# tottag.net
KiCad netlist of a schematic drawn in EAGLE
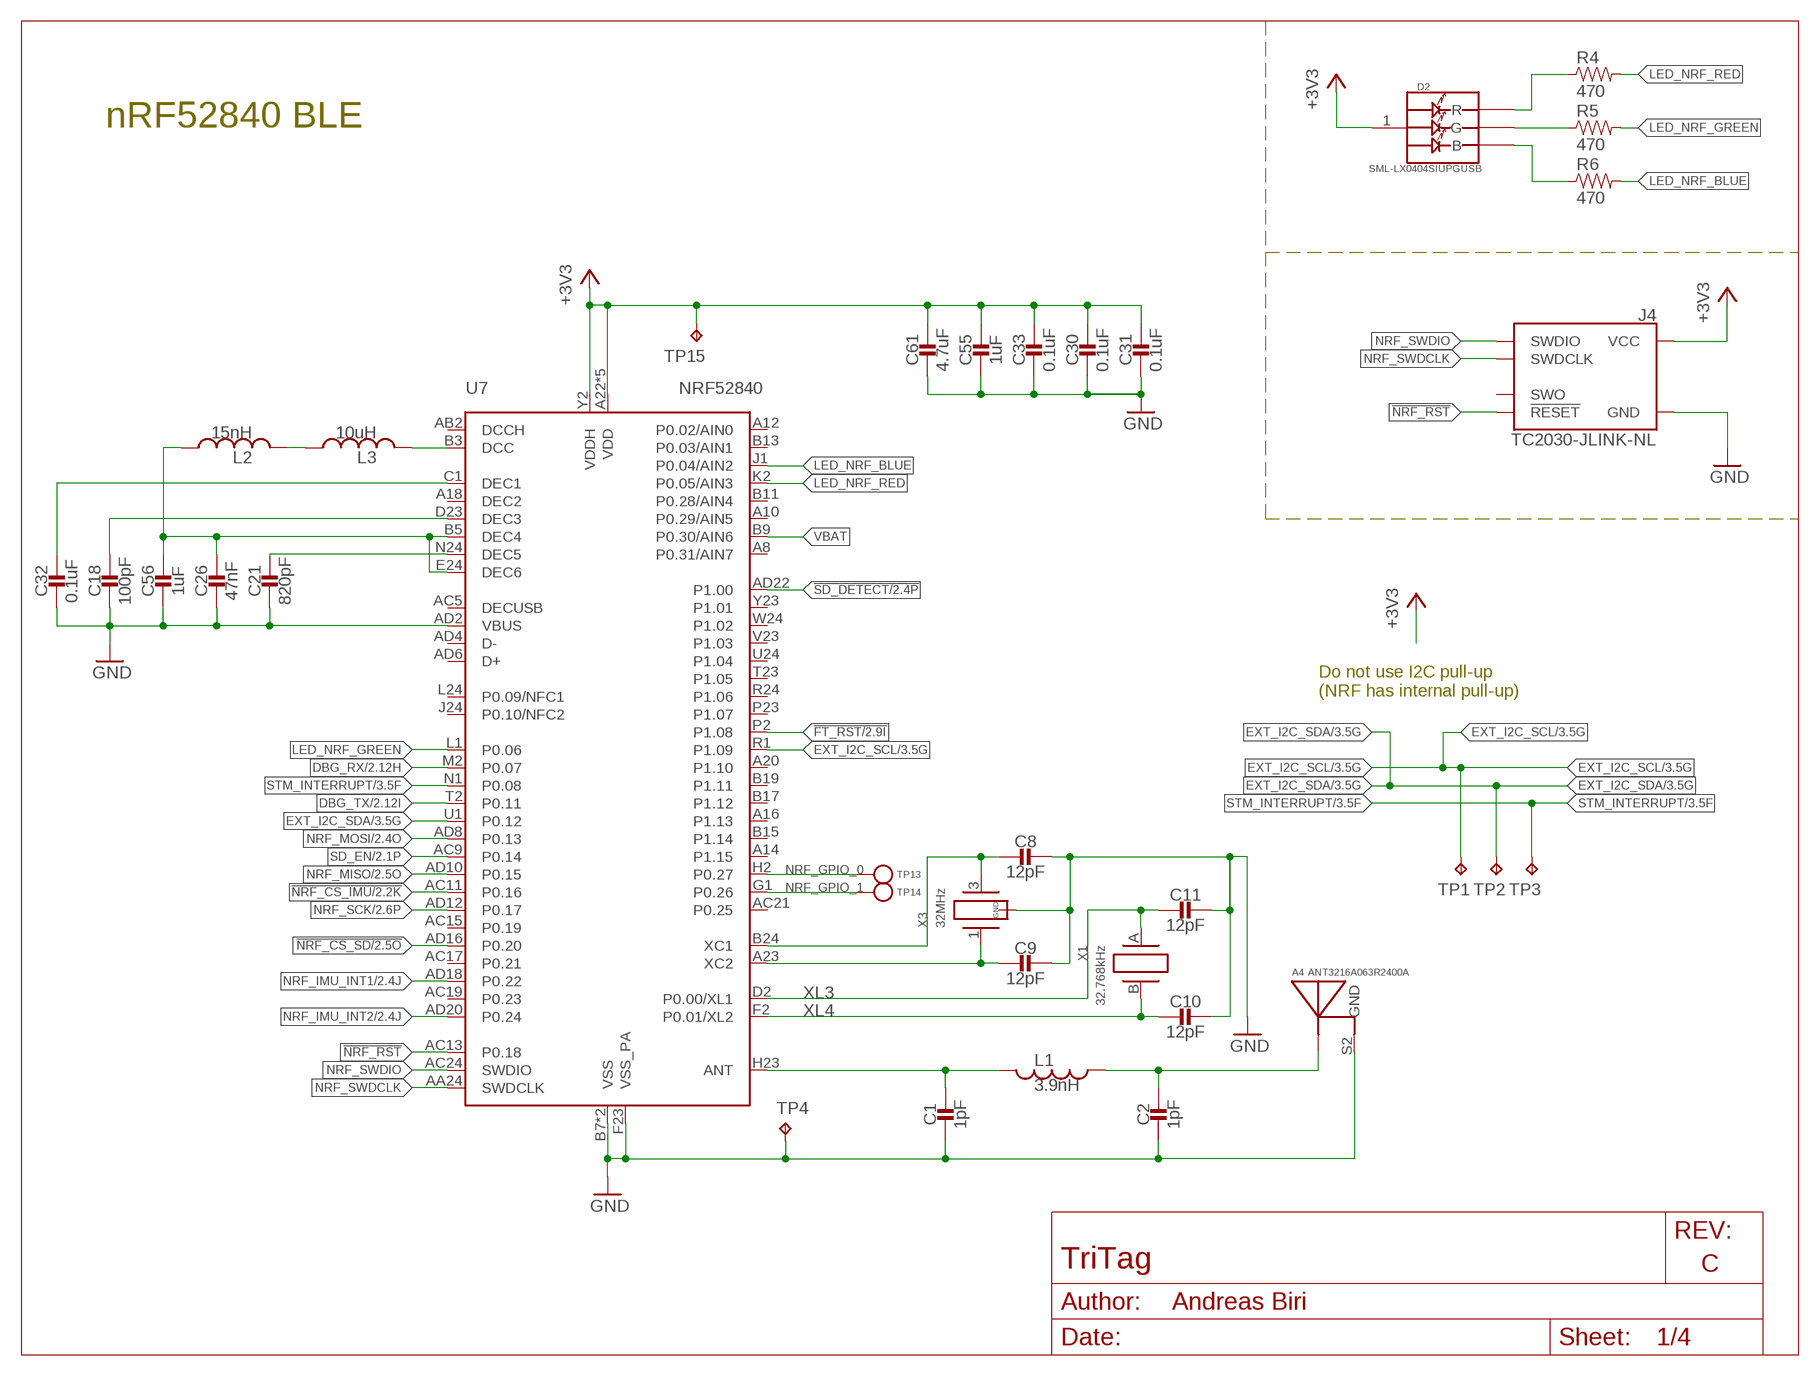
[diagram p0: schematic, sheet 1]
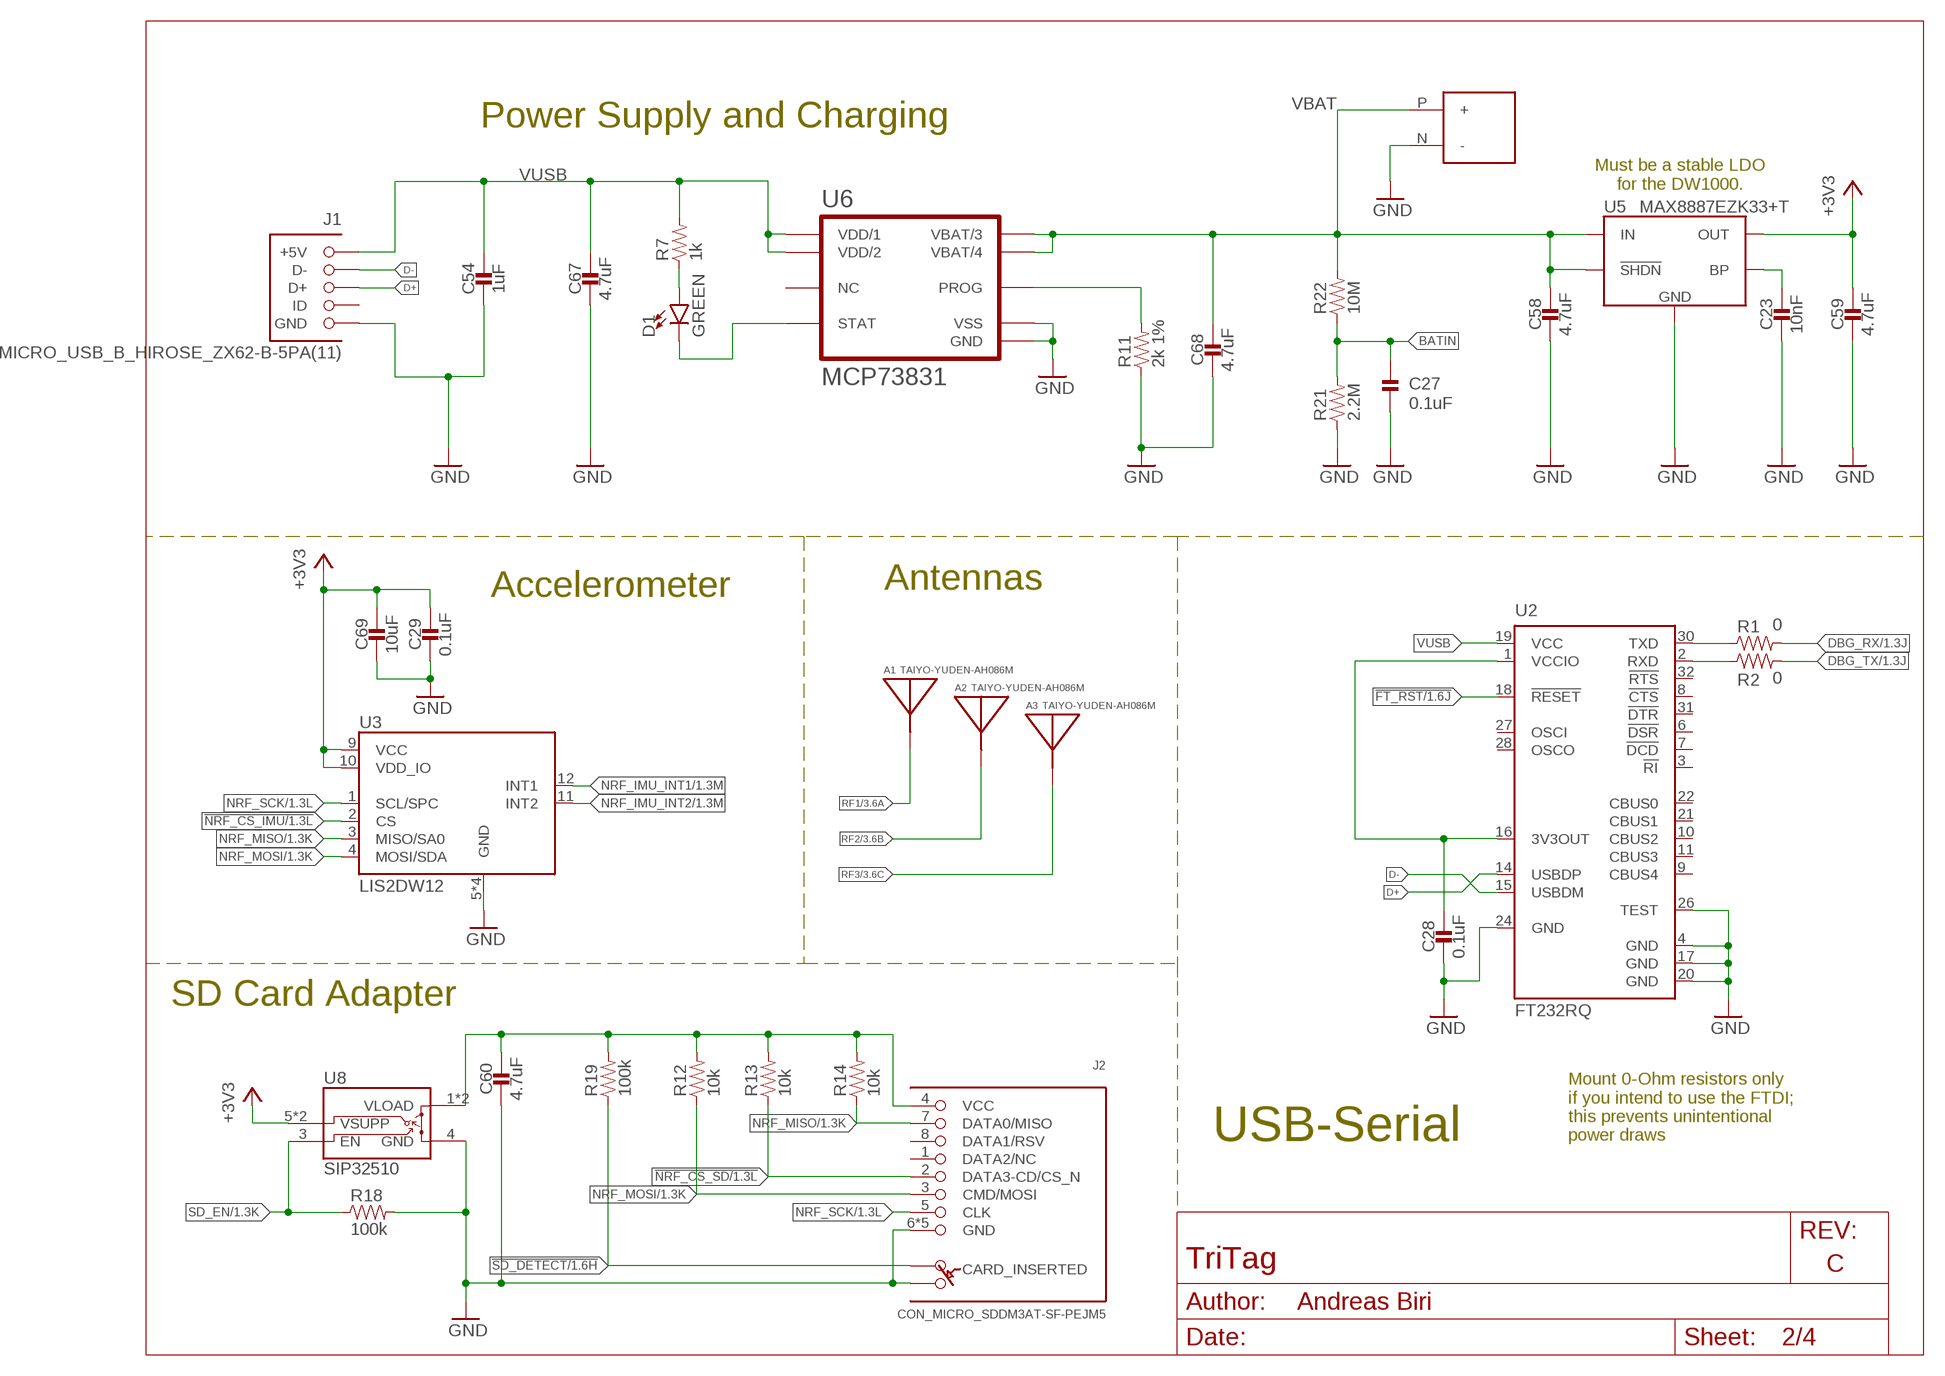
[diagram p1: schematic, sheet 2]
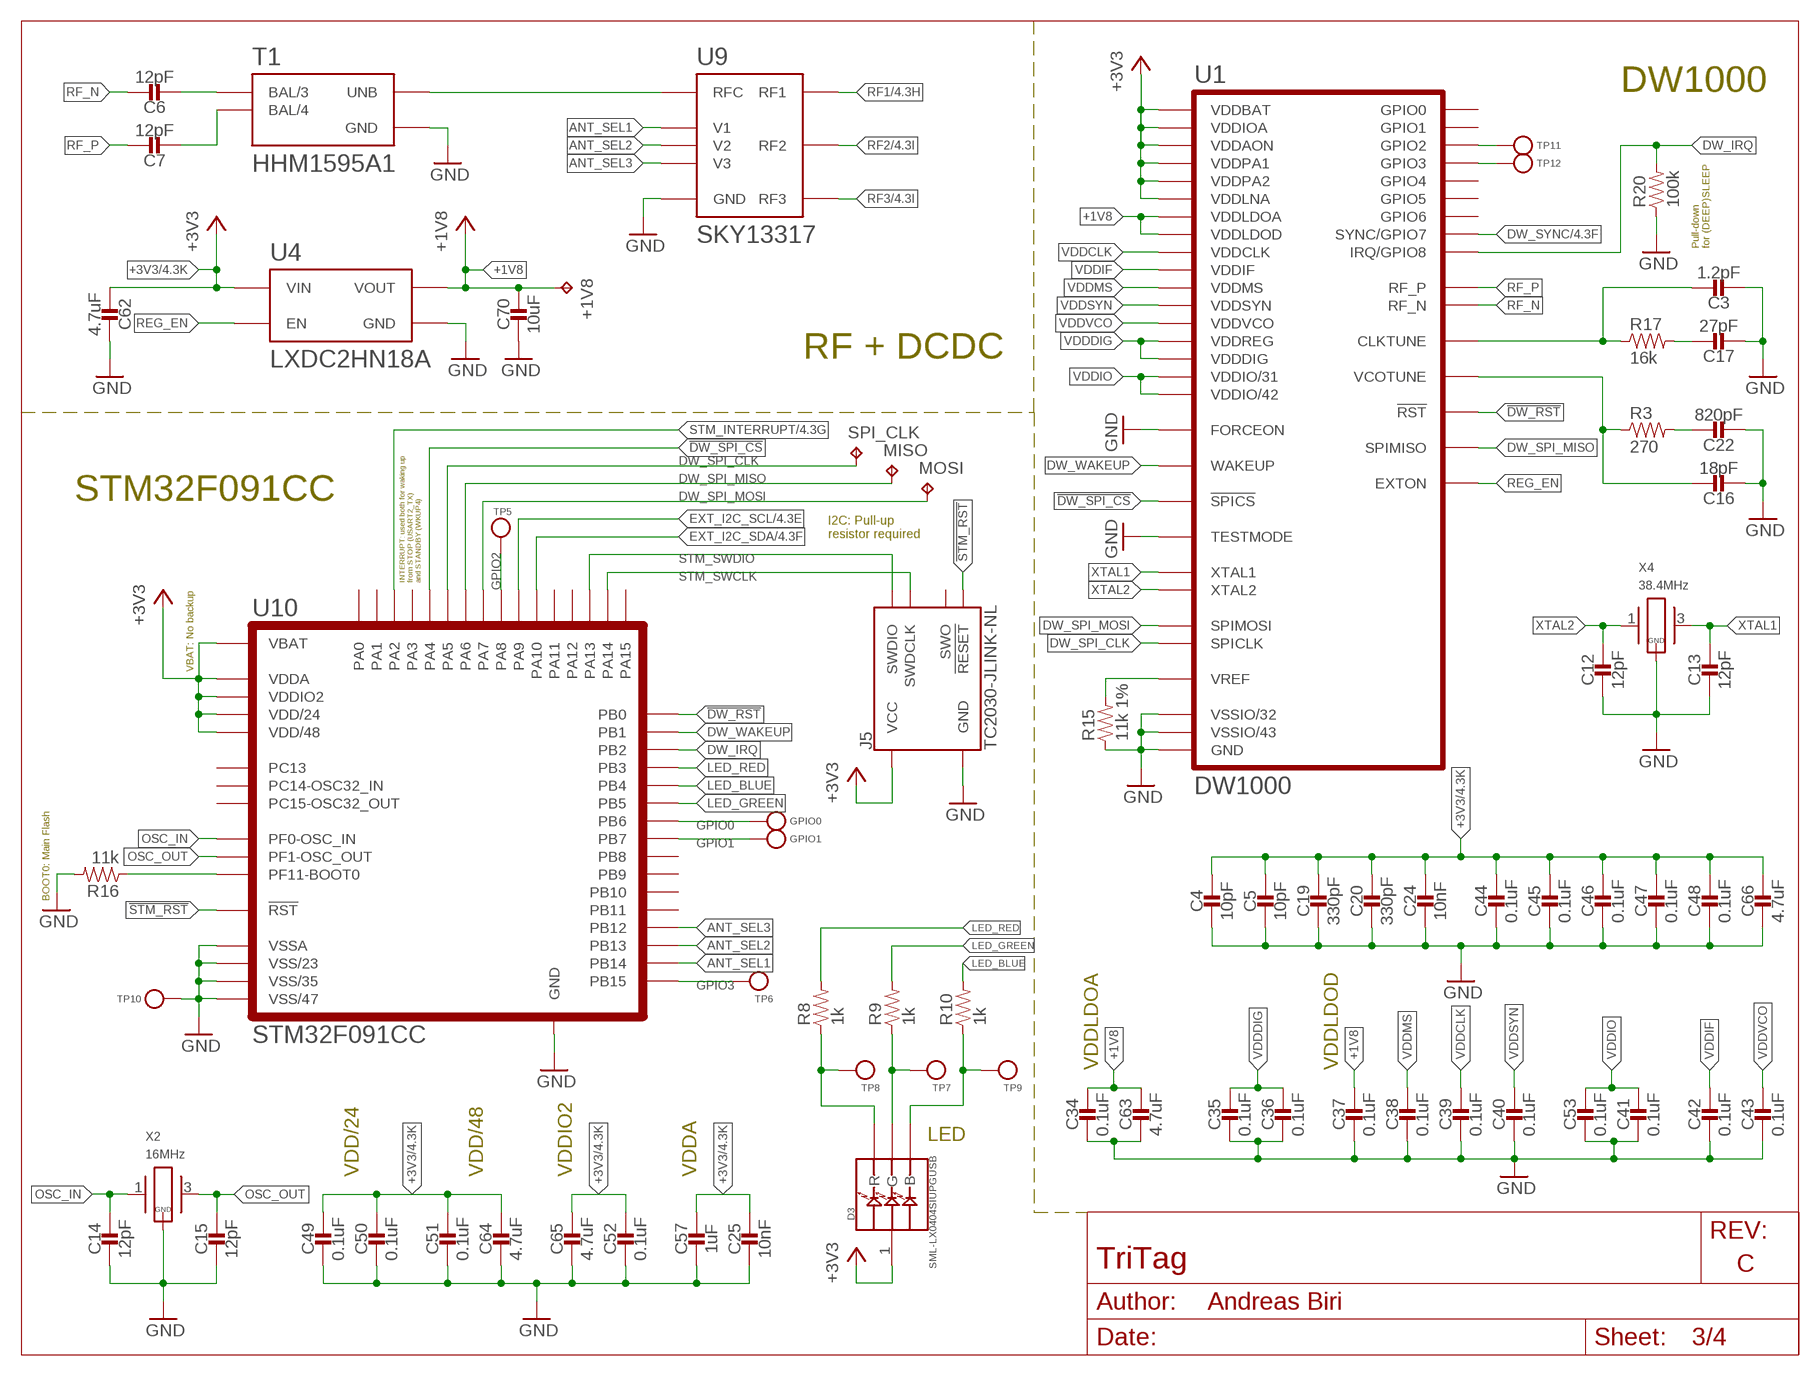
[diagram p2: schematic, sheet 3]
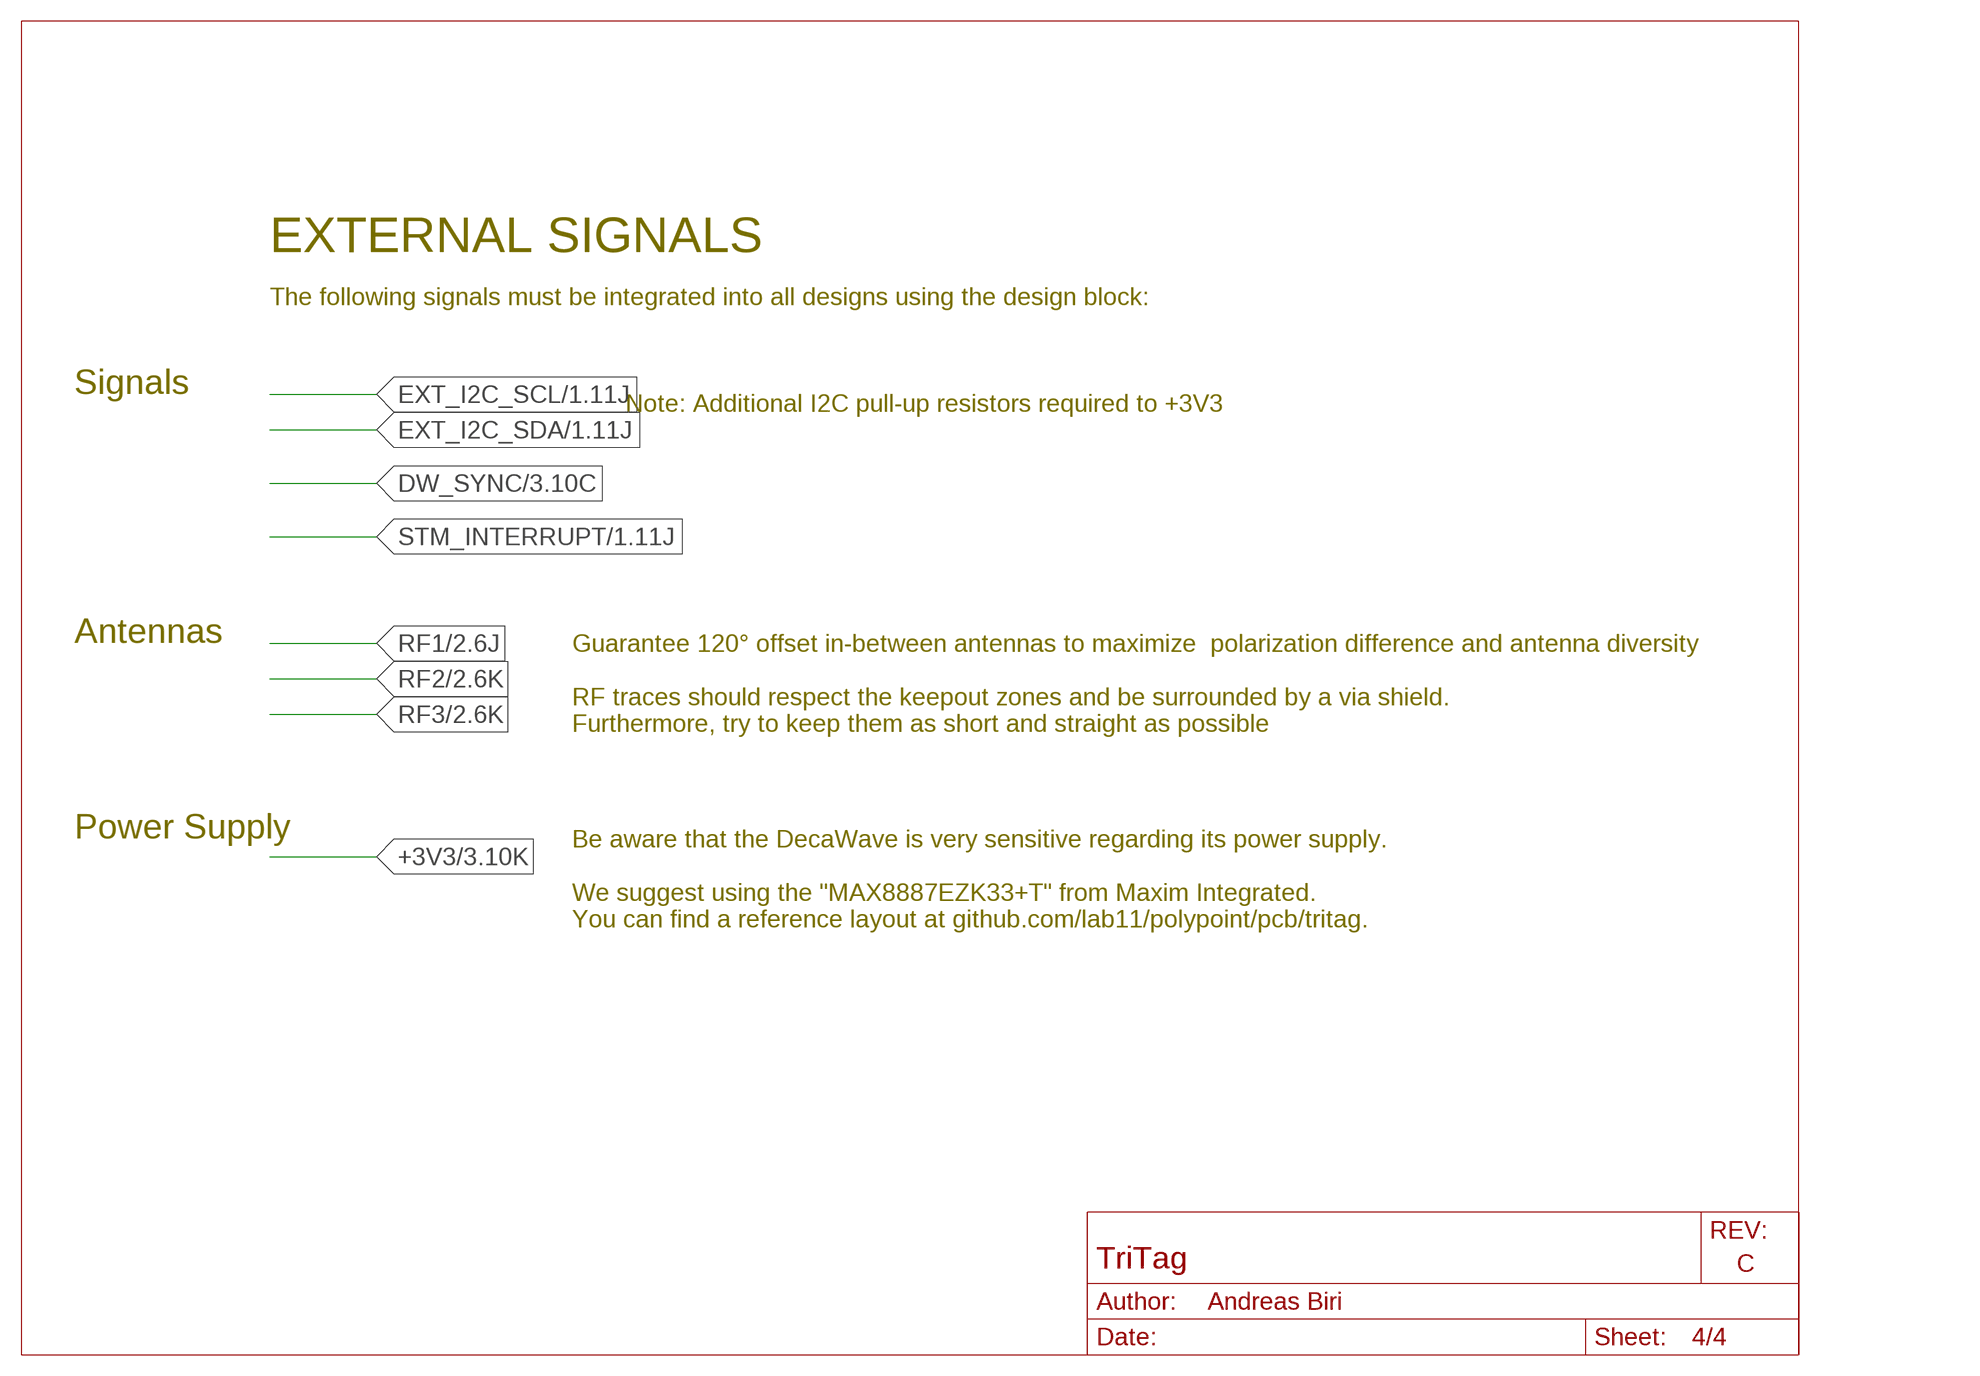
[diagram p3: schematic, sheet 4]

(export (version "E")
  (design (tool "Eeschema 10.0.6"))
  (components
    (comp (ref "A1")
      (value "TAIYO-YUDEN-AH086M")
      (footprint "eagle-import:TAIYO-YUDEN-AH086M")
      (libsource (lib "eagle-import") (part "TAIYO-YUDEN-AH086M"))
    )
    (comp (ref "A2")
      (value "TAIYO-YUDEN-AH086M")
      (footprint "eagle-import:TAIYO-YUDEN-AH086M")
      (libsource (lib "eagle-import") (part "TAIYO-YUDEN-AH086M"))
    )
    (comp (ref "A3")
      (value "TAIYO-YUDEN-AH086M")
      (footprint "eagle-import:TAIYO-YUDEN-AH086M")
      (libsource (lib "eagle-import") (part "TAIYO-YUDEN-AH086M"))
    )
    (comp (ref "C23")
      (value "10nF")
      (footprint "eagle-import:0402_CAP")
      (libsource (lib "eagle-import") (part "CAPACITOR0402_CAP"))
    )
    (comp (ref "C27")
      (value "0.1uF")
      (footprint "eagle-import:0402_CAP")
      (libsource (lib "eagle-import") (part "CAPACITOR0402_CAP"))
    )
    (comp (ref "C28")
      (value "0.1uF")
      (footprint "eagle-import:0402_CAP")
      (fields (field (name "MPN") "GRM155R71C104KA88J "))
      (libsource (lib "eagle-import") (part "CAPACITOR0402_CAP"))
    )
    (comp (ref "C29")
      (value "0.1uF")
      (footprint "eagle-import:0402_CAP")
      (fields (field (name "MPN") "GRM155R71C104KA88J "))
      (libsource (lib "eagle-import") (part "CAPACITOR0402_CAP"))
    )
    (comp (ref "C54")
      (value "1uF")
      (footprint "eagle-import:0402_CAP")
      (libsource (lib "eagle-import") (part "CAPACITOR0402_CAP"))
    )
    (comp (ref "C58")
      (value "4.7uF")
      (footprint "eagle-import:0402_CAP")
      (libsource (lib "eagle-import") (part "CAPACITOR0402_CAP"))
    )
    (comp (ref "C59")
      (value "4.7uF")
      (footprint "eagle-import:0402_CAP")
      (libsource (lib "eagle-import") (part "CAPACITOR0402_CAP"))
    )
    (comp (ref "C60")
      (value "4.7uF")
      (footprint "eagle-import:0402_CAP")
      (description "CAP CER 4.7UF 6.3V X5R 0402")
      (fields (field (name "MANUFACTURER") "TDK") (field (name "MPN") "C1005X5R0J475K050BC"))
      (libsource (lib "eagle-import") (part "CAPACITOR0402_CAP"))
    )
    (comp (ref "C67")
      (value "4.7uF")
      (footprint "eagle-import:0402_CAP")
      (libsource (lib "eagle-import") (part "CAPACITOR0402_CAP"))
    )
    (comp (ref "C68")
      (value "4.7uF")
      (footprint "eagle-import:0402_CAP")
      (libsource (lib "eagle-import") (part "CAPACITOR0402_CAP"))
    )
    (comp (ref "C69")
      (value "10uF")
      (footprint "eagle-import:0603_CAP")
      (fields (field (name "MPN") "GRM188R60J106ME47D "))
      (libsource (lib "eagle-import") (part "CAPACITOR0603_CAP"))
    )
    (comp (ref "D1")
      (value "GREEN")
      (footprint "eagle-import:LED-0603")
      (libsource (lib "eagle-import") (part "LED0603"))
    )
    (comp (ref "J1")
      (value "MICRO_USB_B_HIROSE_ZX62-B-5PA(11)")
      (footprint "eagle-import:USB_MICRO_B-HIROSE-ZX62-B-5PA(11)")
      (libsource (lib "eagle-import") (part "MICRO_USB_B_HIROSE_ZX62-B-5PA(11)"))
    )
    (comp (ref "J2")
      (value "CON_MICRO_SDDM3AT-SF-PEJM5")
      (footprint "eagle-import:DM3AT-SF-PEJM5")
      (libsource (lib "eagle-import") (part "CON_MICRO_SDDM3AT-SF-PEJM5"))
    )
    (comp (ref "J3")
      (value "BAT_HOLE")
      (footprint "eagle-import:BATTERY_HOLE")
      (libsource (lib "eagle-import") (part "BAT_HOLE"))
    )
    (comp (ref "R1")
      (value "0")
      (footprint "eagle-import:0402_RES")
      (libsource (lib "eagle-import") (part "RESISTOR0402_RES"))
    )
    (comp (ref "R2")
      (value "0")
      (footprint "eagle-import:0402_RES")
      (libsource (lib "eagle-import") (part "RESISTOR0402_RES"))
    )
    (comp (ref "R7")
      (value "1k")
      (footprint "eagle-import:0402_RES")
      (libsource (lib "eagle-import") (part "RESISTOR0402_RES"))
    )
    (comp (ref "R11")
      (value "2k 1%")
      (footprint "eagle-import:0402_RES")
      (libsource (lib "eagle-import") (part "RESISTOR0402_RES"))
    )
    (comp (ref "R12")
      (value "10k")
      (footprint "eagle-import:0402_RES")
      (libsource (lib "eagle-import") (part "RESISTOR0402_RES"))
    )
    (comp (ref "R13")
      (value "10k")
      (footprint "eagle-import:0402_RES")
      (libsource (lib "eagle-import") (part "RESISTOR0402_RES"))
    )
    (comp (ref "R14")
      (value "10k")
      (footprint "eagle-import:0402_RES")
      (libsource (lib "eagle-import") (part "RESISTOR0402_RES"))
    )
    (comp (ref "R18")
      (value "100k")
      (footprint "eagle-import:0402_RES")
      (libsource (lib "eagle-import") (part "RESISTOR0402_RES"))
    )
    (comp (ref "R19")
      (value "100k")
      (footprint "eagle-import:0402_RES")
      (libsource (lib "eagle-import") (part "RESISTOR0402_RES"))
    )
    (comp (ref "R21")
      (value "2.2M")
      (footprint "eagle-import:0402_RES")
      (libsource (lib "eagle-import") (part "RESISTOR0402_RES"))
    )
    (comp (ref "R22")
      (value "10M")
      (footprint "eagle-import:0402_RES")
      (libsource (lib "eagle-import") (part "RESISTOR0402_RES"))
    )
    (comp (ref "U2")
      (value "FT232RQ")
      (footprint "eagle-import:QFN32")
      (libsource (lib "eagle-import") (part "FT232RQ"))
    )
    (comp (ref "U3")
      (value "LIS2DW12")
      (footprint "eagle-import:LGA-12")
      (fields (field (name "MANUFACTURER") "STMicroelectronics") (field (name "MPN") "LIS2DW12TR"))
      (libsource (lib "eagle-import") (part "LIS2DW12"))
    )
    (comp (ref "U5")
      (value "MAX8887EZK33+T")
      (footprint "eagle-import:SOT-23-5")
      (libsource (lib "eagle-import") (part "MAX8887EZK33+T"))
    )
    (comp (ref "U6")
      (value "MCP73831")
      (footprint "eagle-import:DFN-8-MCP")
      (fields (field (name "MANUFACTURER") "Microchip Technology") (field (name "MPN") "MCP73831T-2ACI/MC"))
      (libsource (lib "eagle-import") (part "MCP73831"))
    )
    (comp (ref "U8")
      (value "SIP32510")
      (footprint "eagle-import:TSOT23-6")
      (fields (field (name "MANUFACTURER") "Vishay") (field (name "MPN") "SIP32510DT-T1-GE3"))
      (libsource (lib "eagle-import") (part "SIP32510"))
    )
    (comp (ref "A4")
      (value "ANT3216A063R2400A")
      (footprint "eagle-import:ANT3216A063R2400A")
      (fields (field (name "MANUFACTURER") "YAGEO"))
      (libsource (lib "eagle-import") (part "ANT3216A063R2400A"))
    )
    (comp (ref "C1")
      (value "1pF")
      (footprint "eagle-import:0402_CAP")
      (fields (field (name "MPN") "GJM1555C1H1R0CB01D "))
      (libsource (lib "eagle-import") (part "CAPACITOR0402_CAP"))
    )
    (comp (ref "C2")
      (value "1pF")
      (footprint "eagle-import:0402_CAP")
      (fields (field (name "MPN") "GJM1555C1H1R0CB01D"))
      (libsource (lib "eagle-import") (part "CAPACITOR0402_CAP"))
    )
    (comp (ref "C8")
      (value "12pF")
      (footprint "eagle-import:0402_CAP")
      (fields (field (name "MPN") "GRM1555C1H120GA01D "))
      (libsource (lib "eagle-import") (part "CAPACITOR0402_CAP"))
    )
    (comp (ref "C9")
      (value "12pF")
      (footprint "eagle-import:0402_CAP")
      (fields (field (name "MPN") "GRM1555C1H120GA01D "))
      (libsource (lib "eagle-import") (part "CAPACITOR0402_CAP"))
    )
    (comp (ref "C10")
      (value "12pF")
      (footprint "eagle-import:0402_CAP")
      (fields (field (name "MPN") "GRM1555C1H120GA01D "))
      (libsource (lib "eagle-import") (part "CAPACITOR0402_CAP"))
    )
    (comp (ref "C11")
      (value "12pF")
      (footprint "eagle-import:0402_CAP")
      (fields (field (name "MPN") "GRM1555C1H120GA01D "))
      (libsource (lib "eagle-import") (part "CAPACITOR0402_CAP"))
    )
    (comp (ref "C18")
      (value "100pF")
      (footprint "eagle-import:0402_CAP")
      (fields (field (name "MPN") "GRM1555C1H101JA01D "))
      (libsource (lib "eagle-import") (part "CAPACITOR0402_CAP"))
    )
    (comp (ref "C21")
      (value "820pF")
      (footprint "eagle-import:0402_CAP")
      (fields (field (name "MPN") "CL05C821JB5NFNC"))
      (libsource (lib "eagle-import") (part "CAPACITOR0402_CAP"))
    )
    (comp (ref "C26")
      (value "47nF")
      (footprint "eagle-import:0402_CAP")
      (fields (field (name "MPN") "C1005X7R1C473K050BC "))
      (libsource (lib "eagle-import") (part "CAPACITOR0402_CAP"))
    )
    (comp (ref "C30")
      (value "0.1uF")
      (footprint "eagle-import:0402_CAP")
      (fields (field (name "MPN") "GRM155R71C104KA88J "))
      (libsource (lib "eagle-import") (part "CAPACITOR0402_CAP"))
    )
    (comp (ref "C31")
      (value "0.1uF")
      (footprint "eagle-import:0402_CAP")
      (fields (field (name "MPN") "GRM155R71C104KA88J "))
      (libsource (lib "eagle-import") (part "CAPACITOR0402_CAP"))
    )
    (comp (ref "C32")
      (value "0.1uF")
      (footprint "eagle-import:0402_CAP")
      (fields (field (name "MPN") "GRM155R71C104KA88J "))
      (libsource (lib "eagle-import") (part "CAPACITOR0402_CAP"))
    )
    (comp (ref "C33")
      (value "0.1uF")
      (footprint "eagle-import:0402_CAP")
      (fields (field (name "MPN") "GRM155R71C104KA88J "))
      (libsource (lib "eagle-import") (part "CAPACITOR0402_CAP"))
    )
    (comp (ref "C55")
      (value "1uF")
      (footprint "eagle-import:0402_CAP")
      (fields (field (name "MPN") "GRM155R70G105KA12D "))
      (libsource (lib "eagle-import") (part "CAPACITOR0402_CAP"))
    )
    (comp (ref "C56")
      (value "1uF")
      (footprint "eagle-import:0402_CAP")
      (fields (field (name "MPN") "GRM155R70G105KA12D "))
      (libsource (lib "eagle-import") (part "CAPACITOR0402_CAP"))
    )
    (comp (ref "C61")
      (value "4.7uF")
      (footprint "eagle-import:0402_CAP")
      (fields (field (name "MPN") "C1005X5R0J475K050BC "))
      (libsource (lib "eagle-import") (part "CAPACITOR0402_CAP"))
    )
    (comp (ref "D2")
      (value "SML-LX0404SIUPGUSB")
      (footprint "eagle-import:1MM_SQ_4PAD")
      (fields (field (name "MANUFACTURER") "Lumex Opto"))
      (libsource (lib "eagle-import") (part "SML-LX0404SIUPGUSB"))
    )
    (comp (ref "J4")
      (value "TC2030-JLINK-NL")
      (footprint "eagle-import:TC2030-IDC-NL")
      (libsource (lib "eagle-import") (part "TC2030-JLINK-NL"))
    )
    (comp (ref "L1")
      (value "3.9nH")
      (footprint "eagle-import:0402_CAP")
      (fields (field (name "MPN") "AISC-0402-3N9G-T "))
      (libsource (lib "eagle-import") (part "INDUCTOR0402"))
    )
    (comp (ref "L2")
      (value "15nH")
      (footprint "eagle-import:0402_CAP")
      (fields (field (name "MPN") "HK100515NJ-T "))
      (libsource (lib "eagle-import") (part "INDUCTOR0402"))
    )
    (comp (ref "L3")
      (value "10uH")
      (footprint "eagle-import:0603_CAP")
      (fields (field (name "MPN") "LQM18FN100M00D "))
      (libsource (lib "eagle-import") (part "INDUCTOR0603"))
    )
    (comp (ref "R4")
      (value "470")
      (footprint "eagle-import:0402_RES")
      (libsource (lib "eagle-import") (part "RESISTOR0402_RES"))
    )
    (comp (ref "R5")
      (value "470")
      (footprint "eagle-import:0402_RES")
      (libsource (lib "eagle-import") (part "RESISTOR0402_RES"))
    )
    (comp (ref "R6")
      (value "470")
      (footprint "eagle-import:0402_RES")
      (libsource (lib "eagle-import") (part "RESISTOR0402_RES"))
    )
    (comp (ref "TP1")
      (value "TPTP06SQ")
      (footprint "eagle-import:TP06SQ")
      (libsource (lib "eagle-import") (part "TPTP06SQ"))
    )
    (comp (ref "TP2")
      (value "TPTP06SQ")
      (footprint "eagle-import:TP06SQ")
      (libsource (lib "eagle-import") (part "TPTP06SQ"))
    )
    (comp (ref "TP3")
      (value "TPTP06SQ")
      (footprint "eagle-import:TP06SQ")
      (libsource (lib "eagle-import") (part "TPTP06SQ"))
    )
    (comp (ref "TP4")
      (value "TPTP06SQ")
      (footprint "eagle-import:TP06SQ")
      (libsource (lib "eagle-import") (part "TPTP06SQ"))
    )
    (comp (ref "TP13")
      (value "TEST-POINT")
      (footprint "eagle-import:PAD.03X.03")
      (libsource (lib "eagle-import") (part "TEST-POINT"))
    )
    (comp (ref "TP14")
      (value "TEST-POINT")
      (footprint "eagle-import:PAD.03X.03")
      (libsource (lib "eagle-import") (part "TEST-POINT"))
    )
    (comp (ref "TP15")
      (value "TPTP06SQ")
      (footprint "eagle-import:TP06SQ")
      (libsource (lib "eagle-import") (part "TPTP06SQ"))
    )
    (comp (ref "U7")
      (value "NRF52840")
      (footprint "eagle-import:AQFN73")
      (fields (field (name "MANUFACTURER") "NORIDIC SEMICONDUCTOR"))
      (libsource (lib "eagle-import") (part "NRF52840"))
    )
    (comp (ref "X1")
      (value "32.768kHz")
      (footprint "eagle-import:ABS05")
      (fields (field (name "MANUFACTURER") "Abracon") (field (name "MPN") "ABS05-32.768KHZ-9-T"))
      (libsource (lib "eagle-import") (part "ABS05-32.768KHZ-9-T"))
    )
    (comp (ref "X3")
      (value "32MHz")
      (footprint "eagle-import:TXC-7V")
      (fields (field (name "MANUFACTURER") "TXC CORPORATION") (field (name "MPN") "7M-32.000MAHV-T"))
      (libsource (lib "eagle-import") (part "7V-32.000MAHV-T"))
    )
    (comp (ref "+1V8")
      (value "TPTP06SQ")
      (footprint "eagle-import:TP06SQ")
      (libsource (lib "eagle-import") (part "TPTP06SQ"))
    )
    (comp (ref "C3")
      (value "1.2pF")
      (footprint "eagle-import:0402_CAP")
      (libsource (lib "eagle-import") (part "CAPACITOR0402_CAP"))
    )
    (comp (ref "C4")
      (value "10pF")
      (footprint "eagle-import:0402_CAP")
      (libsource (lib "eagle-import") (part "CAPACITOR0402_CAP"))
    )
    (comp (ref "C5")
      (value "10pF")
      (footprint "eagle-import:0402_CAP")
      (libsource (lib "eagle-import") (part "CAPACITOR0402_CAP"))
    )
    (comp (ref "C6")
      (value "12pF")
      (footprint "eagle-import:0201_CAP")
      (libsource (lib "eagle-import") (part "CAPACITOR0201_CAP"))
    )
    (comp (ref "C7")
      (value "12pF")
      (footprint "eagle-import:0201_CAP")
      (libsource (lib "eagle-import") (part "CAPACITOR0201_CAP"))
    )
    (comp (ref "C12")
      (value "12pF")
      (footprint "eagle-import:0402_CAP")
      (libsource (lib "eagle-import") (part "CAPACITOR0402_CAP"))
    )
    (comp (ref "C13")
      (value "12pF")
      (footprint "eagle-import:0402_CAP")
      (libsource (lib "eagle-import") (part "CAPACITOR0402_CAP"))
    )
    (comp (ref "C14")
      (value "12pF")
      (footprint "eagle-import:0402_CAP")
      (libsource (lib "eagle-import") (part "CAPACITOR0402_CAP"))
    )
    (comp (ref "C15")
      (value "12pF")
      (footprint "eagle-import:0402_CAP")
      (libsource (lib "eagle-import") (part "CAPACITOR0402_CAP"))
    )
    (comp (ref "C16")
      (value "18pF")
      (footprint "eagle-import:0402_CAP")
      (libsource (lib "eagle-import") (part "CAPACITOR0402_CAP"))
    )
    (comp (ref "C17")
      (value "27pF")
      (footprint "eagle-import:0402_CAP")
      (libsource (lib "eagle-import") (part "CAPACITOR0402_CAP"))
    )
    (comp (ref "C19")
      (value "330pF")
      (footprint "eagle-import:0402_CAP")
      (libsource (lib "eagle-import") (part "CAPACITOR0402_CAP"))
    )
    (comp (ref "C20")
      (value "330pF")
      (footprint "eagle-import:0402_CAP")
      (libsource (lib "eagle-import") (part "CAPACITOR0402_CAP"))
    )
    (comp (ref "C22")
      (value "820pF")
      (footprint "eagle-import:0402_CAP")
      (libsource (lib "eagle-import") (part "CAPACITOR0402_CAP"))
    )
    (comp (ref "C24")
      (value "10nF")
      (footprint "eagle-import:0402_CAP")
      (libsource (lib "eagle-import") (part "CAPACITOR0402_CAP"))
    )
    (comp (ref "C25")
      (value "10nF")
      (footprint "eagle-import:0402_CAP")
      (libsource (lib "eagle-import") (part "CAPACITOR0402_CAP"))
    )
    (comp (ref "C34")
      (value "0.1uF")
      (footprint "eagle-import:0402_CAP")
      (libsource (lib "eagle-import") (part "CAPACITOR0402_CAP"))
    )
    (comp (ref "C35")
      (value "0.1uF")
      (footprint "eagle-import:0402_CAP")
      (libsource (lib "eagle-import") (part "CAPACITOR0402_CAP"))
    )
    (comp (ref "C36")
      (value "0.1uF")
      (footprint "eagle-import:0402_CAP")
      (libsource (lib "eagle-import") (part "CAPACITOR0402_CAP"))
    )
    (comp (ref "C37")
      (value "0.1uF")
      (footprint "eagle-import:0402_CAP")
      (libsource (lib "eagle-import") (part "CAPACITOR0402_CAP"))
    )
    (comp (ref "C38")
      (value "0.1uF")
      (footprint "eagle-import:0402_CAP")
      (libsource (lib "eagle-import") (part "CAPACITOR0402_CAP"))
    )
    (comp (ref "C39")
      (value "0.1uF")
      (footprint "eagle-import:0402_CAP")
      (libsource (lib "eagle-import") (part "CAPACITOR0402_CAP"))
    )
    (comp (ref "C40")
      (value "0.1uF")
      (footprint "eagle-import:0402_CAP")
      (libsource (lib "eagle-import") (part "CAPACITOR0402_CAP"))
    )
    (comp (ref "C41")
      (value "0.1uF")
      (footprint "eagle-import:0402_CAP")
      (libsource (lib "eagle-import") (part "CAPACITOR0402_CAP"))
    )
    (comp (ref "C42")
      (value "0.1uF")
      (footprint "eagle-import:0402_CAP")
      (libsource (lib "eagle-import") (part "CAPACITOR0402_CAP"))
    )
    (comp (ref "C43")
      (value "0.1uF")
      (footprint "eagle-import:0402_CAP")
      (libsource (lib "eagle-import") (part "CAPACITOR0402_CAP"))
    )
    (comp (ref "C44")
      (value "0.1uF")
      (footprint "eagle-import:0402_CAP")
      (libsource (lib "eagle-import") (part "CAPACITOR0402_CAP"))
    )
    (comp (ref "C45")
      (value "0.1uF")
      (footprint "eagle-import:0402_CAP")
      (libsource (lib "eagle-import") (part "CAPACITOR0402_CAP"))
    )
    (comp (ref "C46")
      (value "0.1uF")
      (footprint "eagle-import:0402_CAP")
      (libsource (lib "eagle-import") (part "CAPACITOR0402_CAP"))
    )
    (comp (ref "C47")
      (value "0.1uF")
      (footprint "eagle-import:0402_CAP")
      (libsource (lib "eagle-import") (part "CAPACITOR0402_CAP"))
    )
    (comp (ref "C48")
      (value "0.1uF")
      (footprint "eagle-import:0402_CAP")
      (libsource (lib "eagle-import") (part "CAPACITOR0402_CAP"))
    )
    (comp (ref "C49")
      (value "0.1uF")
      (footprint "eagle-import:0402_CAP")
      (libsource (lib "eagle-import") (part "CAPACITOR0402_CAP"))
    )
    (comp (ref "C50")
      (value "0.1uF")
      (footprint "eagle-import:0402_CAP")
      (libsource (lib "eagle-import") (part "CAPACITOR0402_CAP"))
    )
    (comp (ref "C51")
      (value "0.1uF")
      (footprint "eagle-import:0402_CAP")
      (libsource (lib "eagle-import") (part "CAPACITOR0402_CAP"))
    )
    (comp (ref "C52")
      (value "0.1uF")
      (footprint "eagle-import:0402_CAP")
      (libsource (lib "eagle-import") (part "CAPACITOR0402_CAP"))
    )
    (comp (ref "C53")
      (value "0.1uF")
      (footprint "eagle-import:0402_CAP")
      (libsource (lib "eagle-import") (part "CAPACITOR0402_CAP"))
    )
    (comp (ref "C57")
      (value "1uF")
      (footprint "eagle-import:0402_CAP")
      (libsource (lib "eagle-import") (part "CAPACITOR0402_CAP"))
    )
    (comp (ref "C62")
      (value "4.7uF")
      (footprint "eagle-import:0402_CAP")
      (libsource (lib "eagle-import") (part "CAPACITOR0402_CAP"))
    )
    (comp (ref "C63")
      (value "4.7uF")
      (footprint "eagle-import:0402_CAP")
      (libsource (lib "eagle-import") (part "CAPACITOR0402_CAP"))
    )
    (comp (ref "C64")
      (value "4.7uF")
      (footprint "eagle-import:0402_CAP")
      (libsource (lib "eagle-import") (part "CAPACITOR0402_CAP"))
    )
    (comp (ref "C65")
      (value "4.7uF")
      (footprint "eagle-import:0402_CAP")
      (libsource (lib "eagle-import") (part "CAPACITOR0402_CAP"))
    )
    (comp (ref "C66")
      (value "4.7uF")
      (footprint "eagle-import:0402_CAP")
      (libsource (lib "eagle-import") (part "CAPACITOR0402_CAP"))
    )
    (comp (ref "C70")
      (value "10uF")
      (footprint "eagle-import:0603_CAP")
      (libsource (lib "eagle-import") (part "CAPACITOR0603_CAP"))
    )
    (comp (ref "D3")
      (value "SML-LX0404SIUPGUSB")
      (footprint "eagle-import:1MM_SQ_4PAD")
      (fields (field (name "MANUFACTURER") "Lumex Opto"))
      (libsource (lib "eagle-import") (part "SML-LX0404SIUPGUSB"))
    )
    (comp (ref "GPIO0")
      (value "TEST-POINT")
      (footprint "eagle-import:PAD.03X.03")
      (libsource (lib "eagle-import") (part "TEST-POINT"))
    )
    (comp (ref "GPIO1")
      (value "TEST-POINT")
      (footprint "eagle-import:PAD.03X.03")
      (libsource (lib "eagle-import") (part "TEST-POINT"))
    )
    (comp (ref "J5")
      (value "TC2030-JLINK-NL")
      (footprint "eagle-import:TC2030-IDC-NL")
      (libsource (lib "eagle-import") (part "TC2030-JLINK-NL"))
    )
    (comp (ref "MISO")
      (value "TPTP06SQ")
      (footprint "eagle-import:TP06SQ")
      (libsource (lib "eagle-import") (part "TPTP06SQ"))
    )
    (comp (ref "MOSI")
      (value "TPTP06SQ")
      (footprint "eagle-import:TP06SQ")
      (libsource (lib "eagle-import") (part "TPTP06SQ"))
    )
    (comp (ref "R3")
      (value "270")
      (footprint "eagle-import:0402_RES")
      (libsource (lib "eagle-import") (part "RESISTOR0402_RES"))
    )
    (comp (ref "R8")
      (value "1k")
      (footprint "eagle-import:0402_RES")
      (libsource (lib "eagle-import") (part "RESISTOR0402_RES"))
    )
    (comp (ref "R9")
      (value "1k")
      (footprint "eagle-import:0402_RES")
      (libsource (lib "eagle-import") (part "RESISTOR0402_RES"))
    )
    (comp (ref "R10")
      (value "1k")
      (footprint "eagle-import:0402_RES")
      (libsource (lib "eagle-import") (part "RESISTOR0402_RES"))
    )
    (comp (ref "R15")
      (value "11k 1%")
      (footprint "eagle-import:0402_RES")
      (libsource (lib "eagle-import") (part "RESISTOR0402_RES"))
    )
    (comp (ref "R16")
      (value "11k")
      (footprint "eagle-import:0402_RES")
      (libsource (lib "eagle-import") (part "RESISTOR0402_RES"))
    )
    (comp (ref "R17")
      (value "16k")
      (footprint "eagle-import:0402_RES")
      (libsource (lib "eagle-import") (part "RESISTOR0402_RES"))
    )
    (comp (ref "R20")
      (value "100k")
      (footprint "eagle-import:0402_RES")
      (libsource (lib "eagle-import") (part "RESISTOR0402_RES"))
    )
    (comp (ref "SPI_CLK")
      (value "TPTP06SQ")
      (footprint "eagle-import:TP06SQ")
      (libsource (lib "eagle-import") (part "TPTP06SQ"))
    )
    (comp (ref "T1")
      (value "HHM1595A1")
      (footprint "eagle-import:EIA-0805")
      (fields (field (name "MANUFACTURER") "TDK Corporation"))
      (libsource (lib "eagle-import") (part "HHM1595A1"))
    )
    (comp (ref "TP5")
      (value "TEST-POINT")
      (footprint "eagle-import:PAD.03X.03")
      (libsource (lib "eagle-import") (part "TEST-POINT"))
    )
    (comp (ref "TP6")
      (value "TEST-POINT")
      (footprint "eagle-import:PAD.03X.03")
      (libsource (lib "eagle-import") (part "TEST-POINT"))
    )
    (comp (ref "TP7")
      (value "TEST-POINT")
      (footprint "eagle-import:PAD.03X.03")
      (libsource (lib "eagle-import") (part "TEST-POINT"))
    )
    (comp (ref "TP8")
      (value "TEST-POINT")
      (footprint "eagle-import:PAD.03X.03")
      (libsource (lib "eagle-import") (part "TEST-POINT"))
    )
    (comp (ref "TP9")
      (value "TEST-POINT")
      (footprint "eagle-import:PAD.03X.03")
      (libsource (lib "eagle-import") (part "TEST-POINT"))
    )
    (comp (ref "TP10")
      (value "TEST-POINT")
      (footprint "eagle-import:PAD.03X.03")
      (libsource (lib "eagle-import") (part "TEST-POINT"))
    )
    (comp (ref "TP11")
      (value "TEST-POINT")
      (footprint "eagle-import:PAD.03X.03")
      (libsource (lib "eagle-import") (part "TEST-POINT"))
    )
    (comp (ref "TP12")
      (value "TEST-POINT")
      (footprint "eagle-import:PAD.03X.03")
      (libsource (lib "eagle-import") (part "TEST-POINT"))
    )
    (comp (ref "U1")
      (value "DW1000")
      (footprint "eagle-import:QFN-48-DW1000")
      (fields (field (name "MANUFACTURER") "Decawave Limited") (field (name "MPN") "DW1000-I-TR13"))
      (libsource (lib "eagle-import") (part "DW1000"))
    )
    (comp (ref "U4")
      (value "LXDC2HN18A")
      (footprint "eagle-import:LXDC2HN")
      (fields
        (field (name "MANUFACTURER") "Murata Electronics North America")
        (field (name "MPN") "LXDC2HN18A-097")
      )
      (libsource (lib "eagle-import") (part "LXDC2HN18A"))
    )
    (comp (ref "U9")
      (value "SKY13317")
      (footprint "eagle-import:MLPQ-UT-8")
      (fields (field (name "MANUFACTURER") "Skyworks Solutions Inc.") (field (name "MPN") "SKY13317-373LF"))
      (libsource (lib "eagle-import") (part "SKY13317"))
    )
    (comp (ref "U10")
      (value "STM32F091CC")
      (footprint "eagle-import:UFQFPN-48")
      (fields (field (name "MANUFACTURER") "STMicroelectronics") (field (name "MPN") "STM32F091CCU6"))
      (libsource (lib "eagle-import") (part "STM32F091CC"))
    )
    (comp (ref "X2")
      (value "16MHz")
      (footprint "eagle-import:FA-20H")
      (description "16MHz ±10ppm Crystal 8pF 80 Ohms 4-SMD, No Lead")
      (fields (field (name "MANUFACTURER") "EPSON"))
      (libsource (lib "eagle-import") (part "FA-20H"))
    )
    (comp (ref "X4")
      (value "38.4MHz")
      (footprint "eagle-import:FA-20H")
      (description "38.4MHz ±10ppm Crystal 8.5pF 40 Ohms 4-SMD, No Lead")
      (fields (field (name "MANUFACTURER") "EPSON"))
      (libsource (lib "eagle-import") (part "FA-20H"))
    )
  )
  (nets
    (net (code "1") (name "+1V8") (class "Default")
      (node (ref "+1V8") (pin "TP") (pinfunction "TP_TP") (pintype "input"))
      (node (ref "C34") (pin "1") (pinfunction "1_1") (pintype "bidirectional"))
      (node (ref "C37") (pin "1") (pinfunction "1_1") (pintype "bidirectional"))
      (node (ref "C63") (pin "1") (pinfunction "1_1") (pintype "bidirectional"))
      (node (ref "C70") (pin "1") (pinfunction "1_1") (pintype "bidirectional"))
      (node (ref "U1") (pin "26") (pinfunction "VDDLDOD_26") (pintype "power_in"))
      (node (ref "U1") (pin "48") (pinfunction "VDDLDOA_48") (pintype "power_in"))
      (node (ref "U4") (pin "3") (pinfunction "VOUT_3") (pintype "power_in"))
    )
    (net (code "2") (name "+3V3") (class "Default")
      (node (ref "C19") (pin "1") (pinfunction "1_1") (pintype "bidirectional"))
      (node (ref "C20") (pin "1") (pinfunction "1_1") (pintype "bidirectional"))
      (node (ref "C24") (pin "1") (pinfunction "1_1") (pintype "bidirectional"))
      (node (ref "C25") (pin "1") (pinfunction "1_1") (pintype "bidirectional"))
      (node (ref "C29") (pin "1") (pinfunction "1_1") (pintype "bidirectional"))
      (node (ref "C30") (pin "1") (pinfunction "1_1") (pintype "bidirectional"))
      (node (ref "C31") (pin "1") (pinfunction "1_1") (pintype "bidirectional"))
      (node (ref "C33") (pin "1") (pinfunction "1_1") (pintype "bidirectional"))
      (node (ref "C4") (pin "1") (pinfunction "1_1") (pintype "bidirectional"))
      (node (ref "C44") (pin "1") (pinfunction "1_1") (pintype "bidirectional"))
      (node (ref "C45") (pin "1") (pinfunction "1_1") (pintype "bidirectional"))
      (node (ref "C46") (pin "1") (pinfunction "1_1") (pintype "bidirectional"))
      (node (ref "C47") (pin "1") (pinfunction "1_1") (pintype "bidirectional"))
      (node (ref "C48") (pin "1") (pinfunction "1_1") (pintype "bidirectional"))
      (node (ref "C49") (pin "1") (pinfunction "1_1") (pintype "bidirectional"))
      (node (ref "C5") (pin "1") (pinfunction "1_1") (pintype "bidirectional"))
      (node (ref "C50") (pin "1") (pinfunction "1_1") (pintype "bidirectional"))
      (node (ref "C51") (pin "1") (pinfunction "1_1") (pintype "bidirectional"))
      (node (ref "C52") (pin "1") (pinfunction "1_1") (pintype "bidirectional"))
      (node (ref "C55") (pin "1") (pinfunction "1_1") (pintype "bidirectional"))
      (node (ref "C57") (pin "1") (pinfunction "1_1") (pintype "bidirectional"))
      (node (ref "C59") (pin "1") (pinfunction "1_1") (pintype "bidirectional"))
      (node (ref "C61") (pin "1") (pinfunction "1_1") (pintype "bidirectional"))
      (node (ref "C62") (pin "2") (pinfunction "2_2") (pintype "bidirectional"))
      (node (ref "C64") (pin "1") (pinfunction "1_1") (pintype "bidirectional"))
      (node (ref "C65") (pin "1") (pinfunction "1_1") (pintype "bidirectional"))
      (node (ref "C66") (pin "1") (pinfunction "1_1") (pintype "bidirectional"))
      (node (ref "C69") (pin "1") (pinfunction "1_1") (pintype "bidirectional"))
      (node (ref "D2") (pin "1") (pinfunction "VDD_1") (pintype "bidirectional"))
      (node (ref "D3") (pin "1") (pinfunction "VDD_1") (pintype "bidirectional"))
      (node (ref "J4") (pin "1") (pinfunction "VCC_1") (pintype "bidirectional"))
      (node (ref "J5") (pin "1") (pinfunction "VCC_1") (pintype "bidirectional"))
      (node (ref "TP15") (pin "TP") (pinfunction "TP_TP") (pintype "input"))
      (node (ref "U1") (pin "15") (pinfunction "VDDLNA_15") (pintype "power_in"))
      (node (ref "U1") (pin "18") (pinfunction "VDDPA1_18") (pintype "power_in"))
      (node (ref "U1") (pin "19") (pinfunction "VDDPA2_19") (pintype "power_in"))
      (node (ref "U1") (pin "25") (pinfunction "VDDAON_25") (pintype "power_in"))
      (node (ref "U1") (pin "28") (pinfunction "VDDIOA_28") (pintype "power_in"))
      (node (ref "U1") (pin "47") (pinfunction "VDDBAT_47") (pintype "power_in"))
      (node (ref "U10") (pin "1") (pinfunction "VBAT_1") (pintype "power_in"))
      (node (ref "U10") (pin "24") (pinfunction "VDD/24_24") (pintype "power_in"))
      (node (ref "U10") (pin "36") (pinfunction "VDDIO2_36") (pintype "power_in"))
      (node (ref "U10") (pin "48") (pinfunction "VDD/48_48") (pintype "power_in"))
      (node (ref "U10") (pin "9") (pinfunction "VDDA_9") (pintype "power_in"))
      (node (ref "U3") (pin "10") (pinfunction "VDD_IO_10") (pintype "bidirectional"))
      (node (ref "U3") (pin "9") (pinfunction "VCC_9") (pintype "bidirectional"))
      (node (ref "U4") (pin "1") (pinfunction "VIN_1") (pintype "power_in"))
      (node (ref "U5") (pin "5") (pinfunction "OUT_5") (pintype "bidirectional"))
      (node (ref "U7") (pin "A22") (pinfunction "VDD_A22") (pintype "bidirectional"))
      (node (ref "U7") (pin "AD14") (pinfunction "VDD_AD14") (pintype "bidirectional"))
      (node (ref "U7") (pin "AD23") (pinfunction "VDD_AD23") (pintype "bidirectional"))
      (node (ref "U7") (pin "B1") (pinfunction "VDD_B1") (pintype "bidirectional"))
      (node (ref "U7") (pin "W1") (pinfunction "VDD_W1") (pintype "bidirectional"))
      (node (ref "U7") (pin "Y2") (pinfunction "VDDH_Y2") (pintype "bidirectional"))
      (node (ref "U8") (pin "5") (pinfunction "VSUPP_5") (pintype "bidirectional"))
      (node (ref "U8") (pin "6") (pinfunction "VSUPP_6") (pintype "bidirectional"))
    )
    (net (code "3") (name "ANT_SEL1") (class "Default")
      (node (ref "U10") (pin "27") (pinfunction "PB14_27") (pintype "bidirectional"))
      (node (ref "U9") (pin "3") (pinfunction "V1_3") (pintype "bidirectional"))
    )
    (net (code "4") (name "ANT_SEL2") (class "Default")
      (node (ref "U10") (pin "26") (pinfunction "PB13_26") (pintype "bidirectional"))
      (node (ref "U9") (pin "6") (pinfunction "V2_6") (pintype "bidirectional"))
    )
    (net (code "5") (name "ANT_SEL3") (class "Default")
      (node (ref "U10") (pin "25") (pinfunction "PB12_25") (pintype "bidirectional"))
      (node (ref "U9") (pin "7") (pinfunction "V3_7") (pintype "bidirectional"))
    )
    (net (code "6") (name "BATIN") (class "Default")
      (node (ref "C27") (pin "2") (pinfunction "2_2") (pintype "bidirectional"))
      (node (ref "R21") (pin "2") (pinfunction "2_2") (pintype "passive"))
      (node (ref "R22") (pin "1") (pinfunction "1_1") (pintype "passive"))
    )
    (net (code "7") (name "D+") (class "Default")
      (node (ref "J1") (pin "3") (pinfunction "D+_3") (pintype "bidirectional"))
      (node (ref "U2") (pin "14") (pinfunction "USBDP_14") (pintype "bidirectional"))
    )
    (net (code "8") (name "D-") (class "Default")
      (node (ref "J1") (pin "2") (pinfunction "D-_2") (pintype "bidirectional"))
      (node (ref "U2") (pin "15") (pinfunction "USBDM_15") (pintype "bidirectional"))
    )
    (net (code "9") (name "DBG_RX") (class "Default")
      (node (ref "R1") (pin "2") (pinfunction "2_2") (pintype "passive"))
      (node (ref "U7") (pin "M2") (pinfunction "P0.07_M2") (pintype "bidirectional"))
    )
    (net (code "10") (name "DBG_TX") (class "Default")
      (node (ref "R2") (pin "2") (pinfunction "2_2") (pintype "passive"))
      (node (ref "U7") (pin "T2") (pinfunction "P0.11_T2") (pintype "bidirectional"))
    )
    (net (code "11") (name "DW_IRQ") (class "Default")
      (node (ref "R20") (pin "2") (pinfunction "2_2") (pintype "passive"))
      (node (ref "U1") (pin "45") (pinfunction "IRQ/GPIO8_45") (pintype "bidirectional"))
      (node (ref "U10") (pin "20") (pinfunction "PB2_20") (pintype "bidirectional"))
    )
    (net (code "12") (name "DW_SPI_CLK") (class "Default")
      (node (ref "SPI_CLK") (pin "TP") (pinfunction "TP_TP") (pintype "input"))
      (node (ref "U1") (pin "41") (pinfunction "SPICLK_41") (pintype "input"))
      (node (ref "U10") (pin "15") (pinfunction "PA5_15") (pintype "bidirectional"))
    )
    (net (code "13") (name "DW_SPI_MISO") (class "Default")
      (node (ref "MISO") (pin "TP") (pinfunction "TP_TP") (pintype "input"))
      (node (ref "U1") (pin "40") (pinfunction "SPIMISO_40") (pintype "output"))
      (node (ref "U10") (pin "16") (pinfunction "PA6_16") (pintype "bidirectional"))
    )
    (net (code "14") (name "DW_SPI_MOSI") (class "Default")
      (node (ref "MOSI") (pin "TP") (pinfunction "TP_TP") (pintype "input"))
      (node (ref "U1") (pin "39") (pinfunction "SPIMOSI_39") (pintype "input"))
      (node (ref "U10") (pin "17") (pinfunction "PA7_17") (pintype "bidirectional"))
    )
    (net (code "15") (name "DW_SYNC") (class "Default")
      (node (ref "U1") (pin "29") (pinfunction "SYNC/GPIO7_29") (pintype "bidirectional"))
    )
    (net (code "16") (name "DW_WAKEUP") (class "Default")
      (node (ref "U1") (pin "23") (pinfunction "WAKEUP_23") (pintype "input"))
      (node (ref "U10") (pin "19") (pinfunction "PB1_19") (pintype "bidirectional"))
    )
    (net (code "17") (name "EXT_I2C_SCL") (class "Default")
      (node (ref "TP1") (pin "TP") (pinfunction "TP_TP") (pintype "input"))
      (node (ref "U10") (pin "30") (pinfunction "PA9_30") (pintype "bidirectional"))
      (node (ref "U7") (pin "R1") (pinfunction "P1.09_R1") (pintype "bidirectional"))
    )
    (net (code "18") (name "EXT_I2C_SDA") (class "Default")
      (node (ref "TP2") (pin "TP") (pinfunction "TP_TP") (pintype "input"))
      (node (ref "U10") (pin "31") (pinfunction "PA10_31") (pintype "bidirectional"))
      (node (ref "U7") (pin "U1") (pinfunction "P0.12_U1") (pintype "bidirectional"))
    )
    (net (code "19") (name "GND") (class "Default")
      (node (ref "A4") (pin "S2") (pinfunction "GND_S2") (pintype "bidirectional"))
      (node (ref "C1") (pin "2") (pinfunction "2_2") (pintype "bidirectional"))
      (node (ref "C10") (pin "1") (pinfunction "1_1") (pintype "bidirectional"))
      (node (ref "C11") (pin "1") (pinfunction "1_1") (pintype "bidirectional"))
      (node (ref "C12") (pin "2") (pinfunction "2_2") (pintype "bidirectional"))
      (node (ref "C13") (pin "2") (pinfunction "2_2") (pintype "bidirectional"))
      (node (ref "C14") (pin "2") (pinfunction "2_2") (pintype "bidirectional"))
      (node (ref "C15") (pin "2") (pinfunction "2_2") (pintype "bidirectional"))
      (node (ref "C16") (pin "2") (pinfunction "2_2") (pintype "bidirectional"))
      (node (ref "C17") (pin "2") (pinfunction "2_2") (pintype "bidirectional"))
      (node (ref "C18") (pin "2") (pinfunction "2_2") (pintype "bidirectional"))
      (node (ref "C19") (pin "2") (pinfunction "2_2") (pintype "bidirectional"))
      (node (ref "C2") (pin "2") (pinfunction "2_2") (pintype "bidirectional"))
      (node (ref "C20") (pin "2") (pinfunction "2_2") (pintype "bidirectional"))
      (node (ref "C21") (pin "2") (pinfunction "2_2") (pintype "bidirectional"))
      (node (ref "C22") (pin "2") (pinfunction "2_2") (pintype "bidirectional"))
      (node (ref "C23") (pin "2") (pinfunction "2_2") (pintype "bidirectional"))
      (node (ref "C24") (pin "2") (pinfunction "2_2") (pintype "bidirectional"))
      (node (ref "C25") (pin "2") (pinfunction "2_2") (pintype "bidirectional"))
      (node (ref "C26") (pin "2") (pinfunction "2_2") (pintype "bidirectional"))
      (node (ref "C27") (pin "1") (pinfunction "1_1") (pintype "bidirectional"))
      (node (ref "C28") (pin "2") (pinfunction "2_2") (pintype "bidirectional"))
      (node (ref "C29") (pin "2") (pinfunction "2_2") (pintype "bidirectional"))
      (node (ref "C3") (pin "2") (pinfunction "2_2") (pintype "bidirectional"))
      (node (ref "C30") (pin "2") (pinfunction "2_2") (pintype "bidirectional"))
      (node (ref "C31") (pin "2") (pinfunction "2_2") (pintype "bidirectional"))
      (node (ref "C32") (pin "2") (pinfunction "2_2") (pintype "bidirectional"))
      (node (ref "C33") (pin "2") (pinfunction "2_2") (pintype "bidirectional"))
      (node (ref "C34") (pin "2") (pinfunction "2_2") (pintype "bidirectional"))
      (node (ref "C35") (pin "2") (pinfunction "2_2") (pintype "bidirectional"))
      (node (ref "C36") (pin "2") (pinfunction "2_2") (pintype "bidirectional"))
      (node (ref "C37") (pin "2") (pinfunction "2_2") (pintype "bidirectional"))
      (node (ref "C38") (pin "2") (pinfunction "2_2") (pintype "bidirectional"))
      (node (ref "C39") (pin "2") (pinfunction "2_2") (pintype "bidirectional"))
      (node (ref "C4") (pin "2") (pinfunction "2_2") (pintype "bidirectional"))
      (node (ref "C40") (pin "2") (pinfunction "2_2") (pintype "bidirectional"))
      (node (ref "C41") (pin "2") (pinfunction "2_2") (pintype "bidirectional"))
      (node (ref "C42") (pin "2") (pinfunction "2_2") (pintype "bidirectional"))
      (node (ref "C43") (pin "2") (pinfunction "2_2") (pintype "bidirectional"))
      (node (ref "C44") (pin "2") (pinfunction "2_2") (pintype "bidirectional"))
      (node (ref "C45") (pin "2") (pinfunction "2_2") (pintype "bidirectional"))
      (node (ref "C46") (pin "2") (pinfunction "2_2") (pintype "bidirectional"))
      (node (ref "C47") (pin "2") (pinfunction "2_2") (pintype "bidirectional"))
      (node (ref "C48") (pin "2") (pinfunction "2_2") (pintype "bidirectional"))
      (node (ref "C49") (pin "2") (pinfunction "2_2") (pintype "bidirectional"))
      (node (ref "C5") (pin "2") (pinfunction "2_2") (pintype "bidirectional"))
      (node (ref "C50") (pin "2") (pinfunction "2_2") (pintype "bidirectional"))
      (node (ref "C51") (pin "2") (pinfunction "2_2") (pintype "bidirectional"))
      (node (ref "C52") (pin "2") (pinfunction "2_2") (pintype "bidirectional"))
      (node (ref "C53") (pin "2") (pinfunction "2_2") (pintype "bidirectional"))
      (node (ref "C54") (pin "2") (pinfunction "2_2") (pintype "bidirectional"))
      (node (ref "C55") (pin "2") (pinfunction "2_2") (pintype "bidirectional"))
      (node (ref "C56") (pin "2") (pinfunction "2_2") (pintype "bidirectional"))
      (node (ref "C57") (pin "2") (pinfunction "2_2") (pintype "bidirectional"))
      (node (ref "C58") (pin "2") (pinfunction "2_2") (pintype "bidirectional"))
      (node (ref "C59") (pin "2") (pinfunction "2_2") (pintype "bidirectional"))
      (node (ref "C60") (pin "2") (pinfunction "2_2") (pintype "bidirectional"))
      (node (ref "C61") (pin "2") (pinfunction "2_2") (pintype "bidirectional"))
      (node (ref "C62") (pin "1") (pinfunction "1_1") (pintype "bidirectional"))
      (node (ref "C63") (pin "2") (pinfunction "2_2") (pintype "bidirectional"))
      (node (ref "C64") (pin "2") (pinfunction "2_2") (pintype "bidirectional"))
      (node (ref "C65") (pin "2") (pinfunction "2_2") (pintype "bidirectional"))
      (node (ref "C66") (pin "2") (pinfunction "2_2") (pintype "bidirectional"))
      (node (ref "C67") (pin "2") (pinfunction "2_2") (pintype "bidirectional"))
      (node (ref "C68") (pin "2") (pinfunction "2_2") (pintype "bidirectional"))
      (node (ref "C69") (pin "2") (pinfunction "2_2") (pintype "bidirectional"))
      (node (ref "C70") (pin "2") (pinfunction "2_2") (pintype "bidirectional"))
      (node (ref "C8") (pin "1") (pinfunction "1_1") (pintype "bidirectional"))
      (node (ref "C9") (pin "1") (pinfunction "1_1") (pintype "bidirectional"))
      (node (ref "J1") (pin "5") (pinfunction "GND_5") (pintype "bidirectional"))
      (node (ref "J2") (pin "6") (pinfunction "GND_6") (pintype "bidirectional"))
      (node (ref "J2") (pin "B") (pinfunction "B_B") (pintype "bidirectional"))
      (node (ref "J2") (pin "MOUNT0") (pinfunction "GND_MOUNT0") (pintype "bidirectional"))
      (node (ref "J2") (pin "MOUNT1") (pinfunction "GND_MOUNT1") (pintype "bidirectional"))
      (node (ref "J2") (pin "MOUNT2") (pinfunction "GND_MOUNT2") (pintype "bidirectional"))
      (node (ref "J2") (pin "MOUNT3") (pinfunction "GND_MOUNT3") (pintype "bidirectional"))
      (node (ref "J3") (pin "N") (pinfunction "-_N") (pintype "bidirectional"))
      (node (ref "J4") (pin "5") (pinfunction "GND_5") (pintype "bidirectional"))
      (node (ref "J5") (pin "5") (pinfunction "GND_5") (pintype "bidirectional"))
      (node (ref "R11") (pin "1") (pinfunction "1_1") (pintype "passive"))
      (node (ref "R15") (pin "1") (pinfunction "1_1") (pintype "passive"))
      (node (ref "R16") (pin "2") (pinfunction "2_2") (pintype "passive"))
      (node (ref "R18") (pin "2") (pinfunction "2_2") (pintype "passive"))
      (node (ref "R20") (pin "1") (pinfunction "1_1") (pintype "passive"))
      (node (ref "R21") (pin "1") (pinfunction "1_1") (pintype "passive"))
      (node (ref "T1") (pin "2") (pinfunction "GND_2") (pintype "power_in"))
      (node (ref "T1") (pin "5") (pinfunction "GND_5") (pintype "power_in"))
      (node (ref "TP10") (pin "P$1") (pinfunction "TESTPOINT_P$1") (pintype "bidirectional"))
      (node (ref "TP4") (pin "TP") (pinfunction "TP_TP") (pintype "input"))
      (node (ref "U1") (pin "22") (pinfunction "FORCEON_22") (pintype "input"))
      (node (ref "U1") (pin "32") (pinfunction "VSSIO/32_32") (pintype "bidirectional"))
      (node (ref "U1") (pin "43") (pinfunction "VSSIO/43_43") (pintype "bidirectional"))
      (node (ref "U1") (pin "46") (pinfunction "TESTMODE_46") (pintype "input"))
      (node (ref "U1") (pin "GND") (pinfunction "GND_GND") (pintype "power_in"))
      (node (ref "U10") (pin "23") (pinfunction "VSS/23_23") (pintype "power_in"))
      (node (ref "U10") (pin "35") (pinfunction "VSS/35_35") (pintype "power_in"))
      (node (ref "U10") (pin "47") (pinfunction "VSS/47_47") (pintype "power_in"))
      (node (ref "U10") (pin "8") (pinfunction "VSSA_8") (pintype "power_in"))
      (node (ref "U10") (pin "GND") (pinfunction "GND_GND") (pintype "power_in"))
      (node (ref "U2") (pin "17") (pinfunction "GND_17") (pintype "power_in"))
      (node (ref "U2") (pin "20") (pinfunction "GND_20") (pintype "power_in"))
      (node (ref "U2") (pin "24") (pinfunction "GND_24") (pintype "power_in"))
      (node (ref "U2") (pin "26") (pinfunction "TEST_26") (pintype "input"))
      (node (ref "U2") (pin "4") (pinfunction "GND_4") (pintype "power_in"))
      (node (ref "U3") (pin "5") (pinfunction "GND_5") (pintype "bidirectional"))
      (node (ref "U3") (pin "6") (pinfunction "GND_6") (pintype "bidirectional"))
      (node (ref "U3") (pin "7") (pinfunction "GND_7") (pintype "bidirectional"))
      (node (ref "U3") (pin "8") (pinfunction "GND_8") (pintype "bidirectional"))
      (node (ref "U4") (pin "4") (pinfunction "GND_4") (pintype "power_in"))
      (node (ref "U5") (pin "2") (pinfunction "GND_2") (pintype "bidirectional"))
      (node (ref "U6") (pin "6") (pinfunction "VSS_6") (pintype "power_in"))
      (node (ref "U6") (pin "GND") (pinfunction "GND_GND") (pintype "power_in"))
      (node (ref "U7") (pin "AD2") (pinfunction "VBUS_AD2") (pintype "bidirectional"))
      (node (ref "U7") (pin "B7") (pinfunction "VSS_B7") (pintype "bidirectional"))
      (node (ref "U7") (pin "F23") (pinfunction "VSS_PA_F23") (pintype "bidirectional"))
      (node (ref "U7") (pin "GND") (pinfunction "VSS_GND") (pintype "bidirectional"))
      (node (ref "U8") (pin "4") (pinfunction "GND_4") (pintype "bidirectional"))
      (node (ref "U9") (pin "GND") (pinfunction "GND_GND") (pintype "power_in"))
      (node (ref "X2") (pin "2") (pinfunction "GND_2") (pintype "bidirectional"))
      (node (ref "X2") (pin "4") (pinfunction "GND_4") (pintype "bidirectional"))
      (node (ref "X3") (pin "2") (pinfunction "GND_2") (pintype "bidirectional"))
      (node (ref "X3") (pin "4") (pinfunction "GND_4") (pintype "bidirectional"))
      (node (ref "X4") (pin "2") (pinfunction "GND_2") (pintype "bidirectional"))
      (node (ref "X4") (pin "4") (pinfunction "GND_4") (pintype "bidirectional"))
    )
    (net (code "20") (name "GPIO0") (class "Default")
      (node (ref "GPIO0") (pin "P$1") (pinfunction "TESTPOINT_P$1") (pintype "bidirectional"))
      (node (ref "U10") (pin "42") (pinfunction "PB6_42") (pintype "bidirectional"))
    )
    (net (code "21") (name "GPIO1") (class "Default")
      (node (ref "GPIO1") (pin "P$1") (pinfunction "TESTPOINT_P$1") (pintype "bidirectional"))
      (node (ref "U10") (pin "43") (pinfunction "PB7_43") (pintype "bidirectional"))
    )
    (net (code "22") (name "GPIO2") (class "Default")
      (node (ref "TP5") (pin "P$1") (pinfunction "TESTPOINT_P$1") (pintype "bidirectional"))
      (node (ref "U10") (pin "29") (pinfunction "PA8_29") (pintype "bidirectional"))
    )
    (net (code "23") (name "GPIO3") (class "Default")
      (node (ref "TP6") (pin "P$1") (pinfunction "TESTPOINT_P$1") (pintype "bidirectional"))
      (node (ref "U10") (pin "28") (pinfunction "PB15_28") (pintype "bidirectional"))
    )
    (net (code "24") (name "LED_BLUE") (class "Default")
      (node (ref "R10") (pin "2") (pinfunction "2_2") (pintype "passive"))
      (node (ref "U10") (pin "40") (pinfunction "PB4_40") (pintype "bidirectional"))
    )
    (net (code "25") (name "LED_GREEN") (class "Default")
      (node (ref "R9") (pin "2") (pinfunction "2_2") (pintype "passive"))
      (node (ref "U10") (pin "41") (pinfunction "PB5_41") (pintype "bidirectional"))
    )
    (net (code "26") (name "LED_NRF_BLUE") (class "Default")
      (node (ref "R6") (pin "2") (pinfunction "2_2") (pintype "passive"))
      (node (ref "U7") (pin "J1") (pinfunction "P0.04/AIN2_J1") (pintype "bidirectional"))
    )
    (net (code "27") (name "LED_NRF_GREEN") (class "Default")
      (node (ref "R5") (pin "2") (pinfunction "2_2") (pintype "passive"))
      (node (ref "U7") (pin "L1") (pinfunction "P0.06_L1") (pintype "bidirectional"))
    )
    (net (code "28") (name "LED_NRF_RED") (class "Default")
      (node (ref "R4") (pin "2") (pinfunction "2_2") (pintype "passive"))
      (node (ref "U7") (pin "K2") (pinfunction "P0.05/AIN3_K2") (pintype "bidirectional"))
    )
    (net (code "29") (name "LED_RED") (class "Default")
      (node (ref "R8") (pin "2") (pinfunction "2_2") (pintype "passive"))
      (node (ref "U10") (pin "39") (pinfunction "PB3_39") (pintype "bidirectional"))
    )
    (net (code "30") (name "NRF_GPIO_0") (class "Default")
      (node (ref "TP13") (pin "P$1") (pinfunction "TESTPOINT_P$1") (pintype "bidirectional"))
      (node (ref "U7") (pin "H2") (pinfunction "P0.27_H2") (pintype "bidirectional"))
    )
    (net (code "31") (name "NRF_GPIO_1") (class "Default")
      (node (ref "TP14") (pin "P$1") (pinfunction "TESTPOINT_P$1") (pintype "bidirectional"))
      (node (ref "U7") (pin "G1") (pinfunction "P0.26_G1") (pintype "bidirectional"))
    )
    (net (code "32") (name "NRF_IMU_INT1") (class "Default")
      (node (ref "U3") (pin "12") (pinfunction "INT1_12") (pintype "bidirectional"))
      (node (ref "U7") (pin "AD18") (pinfunction "P0.22_AD18") (pintype "bidirectional"))
    )
    (net (code "33") (name "NRF_IMU_INT2") (class "Default")
      (node (ref "U3") (pin "11") (pinfunction "INT2_11") (pintype "bidirectional"))
      (node (ref "U7") (pin "AD20") (pinfunction "P0.24_AD20") (pintype "bidirectional"))
    )
    (net (code "34") (name "NRF_MISO") (class "Default")
      (node (ref "J2") (pin "7") (pinfunction "DATA0/MISO_7") (pintype "bidirectional"))
      (node (ref "R14") (pin "1") (pinfunction "1_1") (pintype "passive"))
      (node (ref "U3") (pin "3") (pinfunction "MISO/SA0_3") (pintype "bidirectional"))
      (node (ref "U7") (pin "AD10") (pinfunction "P0.15_AD10") (pintype "bidirectional"))
    )
    (net (code "35") (name "NRF_MOSI") (class "Default")
      (node (ref "J2") (pin "3") (pinfunction "CMD/MOSI_3") (pintype "bidirectional"))
      (node (ref "R12") (pin "1") (pinfunction "1_1") (pintype "passive"))
      (node (ref "U3") (pin "4") (pinfunction "MOSI/SDA_4") (pintype "bidirectional"))
      (node (ref "U7") (pin "AD8") (pinfunction "P0.13_AD8") (pintype "bidirectional"))
    )
    (net (code "36") (name "NRF_SCK") (class "Default")
      (node (ref "J2") (pin "5") (pinfunction "CLK_5") (pintype "bidirectional"))
      (node (ref "U3") (pin "1") (pinfunction "SCL/SPC_1") (pintype "bidirectional"))
      (node (ref "U7") (pin "AD12") (pinfunction "P0.17_AD12") (pintype "bidirectional"))
    )
    (net (code "37") (name "NRF_SWDCLK") (class "Default")
      (node (ref "J4") (pin "4") (pinfunction "SWDCLK_4") (pintype "bidirectional"))
      (node (ref "U7") (pin "AA24") (pinfunction "SWDCLK_AA24") (pintype "bidirectional"))
    )
    (net (code "38") (name "NRF_SWDIO") (class "Default")
      (node (ref "J4") (pin "2") (pinfunction "SWDIO_2") (pintype "bidirectional"))
      (node (ref "U7") (pin "AC24") (pinfunction "SWDIO_AC24") (pintype "bidirectional"))
    )
    (net (code "39") (name "Net-(A4-ANTENNA)") (class "Default")
      (node (ref "A4") (pin "S1") (pinfunction "ANTENNA_S1") (pintype "bidirectional"))
      (node (ref "C2") (pin "1") (pinfunction "1_1") (pintype "bidirectional"))
      (node (ref "L1") (pin "1") (pinfunction "1_1") (pintype "bidirectional"))
    )
    (net (code "40") (name "Net-(C6-2)") (class "Default")
      (node (ref "C6") (pin "P$2") (pinfunction "2_P$2") (pintype "bidirectional"))
      (node (ref "T1") (pin "3") (pinfunction "BAL/3_3") (pintype "bidirectional"))
    )
    (net (code "41") (name "Net-(C7-2)") (class "Default")
      (node (ref "C7") (pin "P$2") (pinfunction "2_P$2") (pintype "bidirectional"))
      (node (ref "T1") (pin "4") (pinfunction "BAL/4_4") (pintype "bidirectional"))
    )
    (net (code "42") (name "Net-(C17-Pad1)") (class "Default")
      (node (ref "C17") (pin "1") (pinfunction "1_1") (pintype "bidirectional"))
      (node (ref "R17") (pin "2") (pinfunction "2_2") (pintype "passive"))
    )
    (net (code "43") (name "Net-(C22-Pad1)") (class "Default")
      (node (ref "C22") (pin "1") (pinfunction "1_1") (pintype "bidirectional"))
      (node (ref "R3") (pin "2") (pinfunction "2_2") (pintype "passive"))
    )
    (net (code "44") (name "Net-(D1-PadA)") (class "Default")
      (node (ref "D1") (pin "A") (pinfunction "A_A") (pintype "passive"))
      (node (ref "R7") (pin "1") (pinfunction "1_1") (pintype "passive"))
    )
    (net (code "45") (name "Net-(D2-B)") (class "Default")
      (node (ref "D2") (pin "3") (pinfunction "B_3") (pintype "output"))
      (node (ref "R6") (pin "1") (pinfunction "1_1") (pintype "passive"))
    )
    (net (code "46") (name "Net-(D2-G)") (class "Default")
      (node (ref "D2") (pin "4") (pinfunction "G_4") (pintype "output"))
      (node (ref "R5") (pin "1") (pinfunction "1_1") (pintype "passive"))
    )
    (net (code "47") (name "Net-(D2-R)") (class "Default")
      (node (ref "D2") (pin "2") (pinfunction "R_2") (pintype "output"))
      (node (ref "R4") (pin "1") (pinfunction "1_1") (pintype "passive"))
    )
    (net (code "48") (name "Net-(D3-B)") (class "Default")
      (node (ref "D3") (pin "3") (pinfunction "B_3") (pintype "output"))
      (node (ref "R10") (pin "1") (pinfunction "1_1") (pintype "passive"))
      (node (ref "TP9") (pin "P$1") (pinfunction "TESTPOINT_P$1") (pintype "bidirectional"))
    )
    (net (code "49") (name "Net-(D3-G)") (class "Default")
      (node (ref "D3") (pin "4") (pinfunction "G_4") (pintype "output"))
      (node (ref "R9") (pin "1") (pinfunction "1_1") (pintype "passive"))
      (node (ref "TP7") (pin "P$1") (pinfunction "TESTPOINT_P$1") (pintype "bidirectional"))
    )
    (net (code "50") (name "Net-(D3-R)") (class "Default")
      (node (ref "D3") (pin "2") (pinfunction "R_2") (pintype "output"))
      (node (ref "R8") (pin "1") (pinfunction "1_1") (pintype "passive"))
      (node (ref "TP8") (pin "P$1") (pinfunction "TESTPOINT_P$1") (pintype "bidirectional"))
    )
    (net (code "51") (name "Net-(J2-VCC)") (class "Default")
      (node (ref "C60") (pin "1") (pinfunction "1_1") (pintype "bidirectional"))
      (node (ref "J2") (pin "4") (pinfunction "VCC_4") (pintype "bidirectional"))
      (node (ref "R12") (pin "2") (pinfunction "2_2") (pintype "passive"))
      (node (ref "R13") (pin "2") (pinfunction "2_2") (pintype "passive"))
      (node (ref "R14") (pin "2") (pinfunction "2_2") (pintype "passive"))
      (node (ref "R19") (pin "2") (pinfunction "2_2") (pintype "passive"))
      (node (ref "U8") (pin "1") (pinfunction "VLOAD_1") (pintype "bidirectional"))
      (node (ref "U8") (pin "2") (pinfunction "VLOAD_2") (pintype "bidirectional"))
    )
    (net (code "52") (name "Net-(L2-Pad2)") (class "Default")
      (node (ref "L2") (pin "2") (pinfunction "2_2") (pintype "bidirectional"))
      (node (ref "L3") (pin "1") (pinfunction "1_1") (pintype "bidirectional"))
    )
    (net (code "53") (name "Net-(T1-UNB)") (class "Default")
      (node (ref "T1") (pin "1") (pinfunction "UNB_1") (pintype "bidirectional"))
      (node (ref "U9") (pin "1") (pinfunction "RFC_1") (pintype "bidirectional"))
    )
    (net (code "54") (name "Net-(TP11-TESTPOINT)") (class "Default")
      (node (ref "TP11") (pin "P$1") (pinfunction "TESTPOINT_P$1") (pintype "bidirectional"))
      (node (ref "U1") (pin "36") (pinfunction "GPIO2_36") (pintype "bidirectional"))
    )
    (net (code "55") (name "Net-(TP12-TESTPOINT)") (class "Default")
      (node (ref "TP12") (pin "P$1") (pinfunction "TESTPOINT_P$1") (pintype "bidirectional"))
      (node (ref "U1") (pin "35") (pinfunction "GPIO3_35") (pintype "bidirectional"))
    )
    (net (code "56") (name "Net-(U1-CLKTUNE)") (class "Default")
      (node (ref "C3") (pin "1") (pinfunction "1_1") (pintype "bidirectional"))
      (node (ref "R17") (pin "1") (pinfunction "1_1") (pintype "passive"))
      (node (ref "U1") (pin "8") (pinfunction "CLKTUNE_8") (pintype "bidirectional"))
    )
    (net (code "57") (name "Net-(U1-VCOTUNE)") (class "Default")
      (node (ref "C16") (pin "1") (pinfunction "1_1") (pintype "bidirectional"))
      (node (ref "R3") (pin "1") (pinfunction "1_1") (pintype "passive"))
      (node (ref "U1") (pin "12") (pinfunction "VCOTUNE_12") (pintype "bidirectional"))
    )
    (net (code "58") (name "Net-(U1-VREF)") (class "Default")
      (node (ref "R15") (pin "2") (pinfunction "2_2") (pintype "passive"))
      (node (ref "U1") (pin "5") (pinfunction "VREF_5") (pintype "bidirectional"))
    )
    (net (code "59") (name "Net-(U2-3V3OUT)") (class "Default")
      (node (ref "C28") (pin "1") (pinfunction "1_1") (pintype "bidirectional"))
      (node (ref "U2") (pin "1") (pinfunction "VCCIO_1") (pintype "power_in"))
      (node (ref "U2") (pin "16") (pinfunction "3V3OUT_16") (pintype "output"))
    )
    (net (code "60") (name "Net-(U2-RXD)") (class "Default")
      (node (ref "R2") (pin "1") (pinfunction "1_1") (pintype "passive"))
      (node (ref "U2") (pin "2") (pinfunction "RXD_2") (pintype "input"))
    )
    (net (code "61") (name "Net-(U2-TXD)") (class "Default")
      (node (ref "R1") (pin "1") (pinfunction "1_1") (pintype "passive"))
      (node (ref "U2") (pin "30") (pinfunction "TXD_30") (pintype "output"))
    )
    (net (code "62") (name "Net-(U5-BP)") (class "Default")
      (node (ref "C23") (pin "1") (pinfunction "1_1") (pintype "bidirectional"))
      (node (ref "U5") (pin "4") (pinfunction "BP_4") (pintype "bidirectional"))
    )
    (net (code "63") (name "Net-(U6-PROG)") (class "Default")
      (node (ref "R11") (pin "2") (pinfunction "2_2") (pintype "passive"))
      (node (ref "U6") (pin "8") (pinfunction "PROG_8") (pintype "bidirectional"))
    )
    (net (code "64") (name "Net-(U6-STAT)") (class "Default")
      (node (ref "D1") (pin "C") (pinfunction "C_C") (pintype "passive"))
      (node (ref "U6") (pin "5") (pinfunction "STAT_5") (pintype "bidirectional"))
    )
    (net (code "65") (name "Net-(U7-ANT)") (class "Default")
      (node (ref "C1") (pin "1") (pinfunction "1_1") (pintype "bidirectional"))
      (node (ref "L1") (pin "2") (pinfunction "2_2") (pintype "bidirectional"))
      (node (ref "U7") (pin "H23") (pinfunction "ANT_H23") (pintype "bidirectional"))
    )
    (net (code "66") (name "Net-(U7-DCC)") (class "Default")
      (node (ref "L3") (pin "2") (pinfunction "2_2") (pintype "bidirectional"))
      (node (ref "U7") (pin "B3") (pinfunction "DCC_B3") (pintype "bidirectional"))
    )
    (net (code "67") (name "Net-(U7-DEC1)") (class "Default")
      (node (ref "C32") (pin "1") (pinfunction "1_1") (pintype "bidirectional"))
      (node (ref "U7") (pin "C1") (pinfunction "DEC1_C1") (pintype "bidirectional"))
    )
    (net (code "68") (name "Net-(U7-DEC3)") (class "Default")
      (node (ref "C18") (pin "1") (pinfunction "1_1") (pintype "bidirectional"))
      (node (ref "U7") (pin "D23") (pinfunction "DEC3_D23") (pintype "bidirectional"))
    )
    (net (code "69") (name "Net-(U7-DEC4)") (class "Default")
      (node (ref "C26") (pin "1") (pinfunction "1_1") (pintype "bidirectional"))
      (node (ref "C56") (pin "1") (pinfunction "1_1") (pintype "bidirectional"))
      (node (ref "L2") (pin "1") (pinfunction "1_1") (pintype "bidirectional"))
      (node (ref "U7") (pin "B5") (pinfunction "DEC4_B5") (pintype "bidirectional"))
      (node (ref "U7") (pin "E24") (pinfunction "DEC6_E24") (pintype "bidirectional"))
    )
    (net (code "70") (name "Net-(U7-DEC5)") (class "Default")
      (node (ref "C21") (pin "1") (pinfunction "1_1") (pintype "bidirectional"))
      (node (ref "U7") (pin "N24") (pinfunction "DEC5_N24") (pintype "bidirectional"))
    )
    (net (code "71") (name "Net-(U7-XC1)") (class "Default")
      (node (ref "C8") (pin "2") (pinfunction "2_2") (pintype "bidirectional"))
      (node (ref "U7") (pin "B24") (pinfunction "XC1_B24") (pintype "bidirectional"))
      (node (ref "X3") (pin "3") (pinfunction "2_3") (pintype "bidirectional"))
    )
    (net (code "72") (name "Net-(U7-XC2)") (class "Default")
      (node (ref "C9") (pin "2") (pinfunction "2_2") (pintype "bidirectional"))
      (node (ref "U7") (pin "A23") (pinfunction "XC2_A23") (pintype "bidirectional"))
      (node (ref "X3") (pin "1") (pinfunction "1_1") (pintype "bidirectional"))
    )
    (net (code "73") (name "Net-(U10-PF11-BOOT0)") (class "Default")
      (node (ref "R16") (pin "1") (pinfunction "1_1") (pintype "passive"))
      (node (ref "U10") (pin "44") (pinfunction "PF11-BOOT0_44") (pintype "bidirectional"))
    )
    (net (code "74") (name "OSC_IN") (class "Default")
      (node (ref "C14") (pin "1") (pinfunction "1_1") (pintype "bidirectional"))
      (node (ref "U10") (pin "5") (pinfunction "PF0-OSC_IN_5") (pintype "bidirectional"))
      (node (ref "X2") (pin "1") (pinfunction "1_1") (pintype "bidirectional"))
    )
    (net (code "75") (name "OSC_OUT") (class "Default")
      (node (ref "C15") (pin "1") (pinfunction "1_1") (pintype "bidirectional"))
      (node (ref "U10") (pin "6") (pinfunction "PF1-OSC_OUT_6") (pintype "bidirectional"))
      (node (ref "X2") (pin "3") (pinfunction "2_3") (pintype "bidirectional"))
    )
    (net (code "76") (name "REG_EN") (class "Default")
      (node (ref "U1") (pin "21") (pinfunction "EXTON_21") (pintype "output"))
      (node (ref "U4") (pin "2") (pinfunction "EN_2") (pintype "bidirectional"))
    )
    (net (code "77") (name "RF1") (class "Default")
      (node (ref "A1") (pin "A") (pinfunction "ANTENNA_A") (pintype "bidirectional"))
      (node (ref "U9") (pin "4") (pinfunction "RF1_4") (pintype "bidirectional"))
    )
    (net (code "78") (name "RF2") (class "Default")
      (node (ref "A2") (pin "A") (pinfunction "ANTENNA_A") (pintype "bidirectional"))
      (node (ref "U9") (pin "5") (pinfunction "RF2_5") (pintype "bidirectional"))
    )
    (net (code "79") (name "RF3") (class "Default")
      (node (ref "A3") (pin "A") (pinfunction "ANTENNA_A") (pintype "bidirectional"))
      (node (ref "U9") (pin "8") (pinfunction "RF3_8") (pintype "bidirectional"))
    )
    (net (code "80") (name "RF_N") (class "Default")
      (node (ref "C6") (pin "P$1") (pinfunction "1_P$1") (pintype "bidirectional"))
      (node (ref "U1") (pin "17") (pinfunction "RF_N_17") (pintype "bidirectional"))
    )
    (net (code "81") (name "RF_P") (class "Default")
      (node (ref "C7") (pin "P$1") (pinfunction "1_P$1") (pintype "bidirectional"))
      (node (ref "U1") (pin "16") (pinfunction "RF_P_16") (pintype "bidirectional"))
    )
    (net (code "82") (name "SD_EN") (class "Default")
      (node (ref "R18") (pin "1") (pinfunction "1_1") (pintype "passive"))
      (node (ref "U7") (pin "AC9") (pinfunction "P0.14_AC9") (pintype "bidirectional"))
      (node (ref "U8") (pin "3") (pinfunction "EN_3") (pintype "bidirectional"))
    )
    (net (code "83") (name "STM_INTERRUPT") (class "Default")
      (node (ref "TP3") (pin "TP") (pinfunction "TP_TP") (pintype "input"))
      (node (ref "U10") (pin "12") (pinfunction "PA2_12") (pintype "bidirectional"))
      (node (ref "U7") (pin "N1") (pinfunction "P0.08_N1") (pintype "bidirectional"))
    )
    (net (code "84") (name "STM_SWCLK") (class "Default")
      (node (ref "J5") (pin "4") (pinfunction "SWDCLK_4") (pintype "bidirectional"))
      (node (ref "U10") (pin "37") (pinfunction "PA14_37") (pintype "bidirectional"))
    )
    (net (code "85") (name "STM_SWDIO") (class "Default")
      (node (ref "J5") (pin "2") (pinfunction "SWDIO_2") (pintype "bidirectional"))
      (node (ref "U10") (pin "34") (pinfunction "PA13_34") (pintype "bidirectional"))
    )
    (net (code "86") (name "VBAT") (class "Default")
      (node (ref "C58") (pin "1") (pinfunction "1_1") (pintype "bidirectional"))
      (node (ref "C68") (pin "1") (pinfunction "1_1") (pintype "bidirectional"))
      (node (ref "J3") (pin "P") (pinfunction "+_P") (pintype "bidirectional"))
      (node (ref "R22") (pin "2") (pinfunction "2_2") (pintype "passive"))
      (node (ref "U5") (pin "1") (pinfunction "IN_1") (pintype "bidirectional"))
      (node (ref "U5") (pin "3") (pinfunction "~{SHDN}_3") (pintype "bidirectional"))
      (node (ref "U6") (pin "3") (pinfunction "VBAT/3_3") (pintype "power_in"))
      (node (ref "U6") (pin "4") (pinfunction "VBAT/4_4") (pintype "power_in"))
      (node (ref "U7") (pin "B9") (pinfunction "P0.30/AIN6_B9") (pintype "bidirectional"))
    )
    (net (code "87") (name "VDDCLK") (class "Default")
      (node (ref "C39") (pin "1") (pinfunction "1_1") (pintype "bidirectional"))
      (node (ref "U1") (pin "9") (pinfunction "VDDCLK_9") (pintype "power_in"))
    )
    (net (code "88") (name "VDDDIG") (class "Default")
      (node (ref "C35") (pin "1") (pinfunction "1_1") (pintype "bidirectional"))
      (node (ref "C36") (pin "1") (pinfunction "1_1") (pintype "bidirectional"))
      (node (ref "U1") (pin "20") (pinfunction "VDDREG_20") (pintype "power_in"))
      (node (ref "U1") (pin "44") (pinfunction "VDDDIG_44") (pintype "power_in"))
    )
    (net (code "89") (name "VDDIF") (class "Default")
      (node (ref "C42") (pin "1") (pinfunction "1_1") (pintype "bidirectional"))
      (node (ref "U1") (pin "7") (pinfunction "VDDIF_7") (pintype "power_in"))
    )
    (net (code "90") (name "VDDIO") (class "Default")
      (node (ref "C41") (pin "1") (pinfunction "1_1") (pintype "bidirectional"))
      (node (ref "C53") (pin "1") (pinfunction "1_1") (pintype "bidirectional"))
      (node (ref "U1") (pin "31") (pinfunction "VDDIO/31_31") (pintype "power_in"))
      (node (ref "U1") (pin "42") (pinfunction "VDDIO/42_42") (pintype "power_in"))
    )
    (net (code "91") (name "VDDMS") (class "Default")
      (node (ref "C38") (pin "1") (pinfunction "1_1") (pintype "bidirectional"))
      (node (ref "U1") (pin "6") (pinfunction "VDDMS_6") (pintype "power_in"))
    )
    (net (code "92") (name "VDDSYN") (class "Default")
      (node (ref "C40") (pin "1") (pinfunction "1_1") (pintype "bidirectional"))
      (node (ref "U1") (pin "10") (pinfunction "VDDSYN_10") (pintype "power_in"))
    )
    (net (code "93") (name "VDDVCO") (class "Default")
      (node (ref "C43") (pin "1") (pinfunction "1_1") (pintype "bidirectional"))
      (node (ref "U1") (pin "11") (pinfunction "VDDVCO_11") (pintype "power_in"))
    )
    (net (code "94") (name "VUSB") (class "Default")
      (node (ref "C54") (pin "1") (pinfunction "1_1") (pintype "bidirectional"))
      (node (ref "C67") (pin "1") (pinfunction "1_1") (pintype "bidirectional"))
      (node (ref "J1") (pin "1") (pinfunction "+5V_1") (pintype "bidirectional"))
      (node (ref "R7") (pin "2") (pinfunction "2_2") (pintype "passive"))
      (node (ref "U2") (pin "19") (pinfunction "VCC_19") (pintype "power_in"))
      (node (ref "U6") (pin "1") (pinfunction "VDD/1_1") (pintype "power_in"))
      (node (ref "U6") (pin "2") (pinfunction "VDD/2_2") (pintype "power_in"))
    )
    (net (code "95") (name "XL3") (class "Default")
      (node (ref "C11") (pin "2") (pinfunction "2_2") (pintype "bidirectional"))
      (node (ref "U7") (pin "D2") (pinfunction "P0.00/XL1_D2") (pintype "bidirectional"))
      (node (ref "X1") (pin "A") (pinfunction "1_A") (pintype "bidirectional"))
    )
    (net (code "96") (name "XL4") (class "Default")
      (node (ref "C10") (pin "2") (pinfunction "2_2") (pintype "bidirectional"))
      (node (ref "U7") (pin "F2") (pinfunction "P0.01/XL2_F2") (pintype "bidirectional"))
      (node (ref "X1") (pin "B") (pinfunction "2_B") (pintype "bidirectional"))
    )
    (net (code "97") (name "XTAL1") (class "Default")
      (node (ref "C13") (pin "1") (pinfunction "1_1") (pintype "bidirectional"))
      (node (ref "U1") (pin "3") (pinfunction "XTAL1_3") (pintype "input"))
      (node (ref "X4") (pin "3") (pinfunction "2_3") (pintype "bidirectional"))
    )
    (net (code "98") (name "XTAL2") (class "Default")
      (node (ref "C12") (pin "1") (pinfunction "1_1") (pintype "bidirectional"))
      (node (ref "U1") (pin "4") (pinfunction "XTAL2_4") (pintype "input"))
      (node (ref "X4") (pin "1") (pinfunction "1_1") (pintype "bidirectional"))
    )
    (net (code "99") (name "unconnected-(J1-ID-Pad4)") (class "Default")
      (node (ref "J1") (pin "4") (pinfunction "ID_4") (pintype "bidirectional"))
    )
    (net (code "100") (name "unconnected-(J2-DATA1{slash}RSV-Pad8)") (class "Default")
      (node (ref "J2") (pin "8") (pinfunction "DATA1/RSV_8") (pintype "bidirectional"))
    )
    (net (code "101") (name "unconnected-(J2-DATA2{slash}NC-Pad1)") (class "Default")
      (node (ref "J2") (pin "1") (pinfunction "DATA2/NC_1") (pintype "bidirectional"))
    )
    (net (code "102") (name "unconnected-(J4-SWO-Pad6)") (class "Default")
      (node (ref "J4") (pin "6") (pinfunction "SWO_6") (pintype "bidirectional"))
    )
    (net (code "103") (name "unconnected-(J5-SWO-Pad6)") (class "Default")
      (node (ref "J5") (pin "6") (pinfunction "SWO_6") (pintype "bidirectional"))
    )
    (net (code "104") (name "unconnected-(U1-GPIO0-Pad38)") (class "Default")
      (node (ref "U1") (pin "38") (pinfunction "GPIO0_38") (pintype "bidirectional"))
    )
    (net (code "105") (name "unconnected-(U1-GPIO1-Pad37)") (class "Default")
      (node (ref "U1") (pin "37") (pinfunction "GPIO1_37") (pintype "bidirectional"))
    )
    (net (code "106") (name "unconnected-(U1-GPIO4-Pad34)") (class "Default")
      (node (ref "U1") (pin "34") (pinfunction "GPIO4_34") (pintype "bidirectional"))
    )
    (net (code "107") (name "unconnected-(U1-GPIO5-Pad33)") (class "Default")
      (node (ref "U1") (pin "33") (pinfunction "GPIO5_33") (pintype "bidirectional"))
    )
    (net (code "108") (name "unconnected-(U1-GPIO6-Pad30)") (class "Default")
      (node (ref "U1") (pin "30") (pinfunction "GPIO6_30") (pintype "bidirectional"))
    )
    (net (code "109") (name "unconnected-(U2-CBUS0-Pad22)") (class "Default")
      (node (ref "U2") (pin "22") (pinfunction "CBUS0_22") (pintype "bidirectional"))
    )
    (net (code "110") (name "unconnected-(U2-CBUS1-Pad21)") (class "Default")
      (node (ref "U2") (pin "21") (pinfunction "CBUS1_21") (pintype "bidirectional"))
    )
    (net (code "111") (name "unconnected-(U2-CBUS2-Pad10)") (class "Default")
      (node (ref "U2") (pin "10") (pinfunction "CBUS2_10") (pintype "bidirectional"))
    )
    (net (code "112") (name "unconnected-(U2-CBUS3-Pad11)") (class "Default")
      (node (ref "U2") (pin "11") (pinfunction "CBUS3_11") (pintype "bidirectional"))
    )
    (net (code "113") (name "unconnected-(U2-CBUS4-Pad9)") (class "Default")
      (node (ref "U2") (pin "9") (pinfunction "CBUS4_9") (pintype "bidirectional"))
    )
    (net (code "114") (name "unconnected-(U2-OSCI-Pad27)") (class "Default")
      (node (ref "U2") (pin "27") (pinfunction "OSCI_27") (pintype "input"))
    )
    (net (code "115") (name "unconnected-(U2-OSCO-Pad28)") (class "Default")
      (node (ref "U2") (pin "28") (pinfunction "OSCO_28") (pintype "output"))
    )
    (net (code "116") (name "unconnected-(U2-~{CTS}-Pad8)") (class "Default")
      (node (ref "U2") (pin "8") (pinfunction "~{CTS}_8") (pintype "input"))
    )
    (net (code "117") (name "unconnected-(U2-~{DCD}-Pad7)") (class "Default")
      (node (ref "U2") (pin "7") (pinfunction "~{DCD}_7") (pintype "input"))
    )
    (net (code "118") (name "unconnected-(U2-~{DSR}-Pad6)") (class "Default")
      (node (ref "U2") (pin "6") (pinfunction "~{DSR}_6") (pintype "input"))
    )
    (net (code "119") (name "unconnected-(U2-~{DTR}-Pad31)") (class "Default")
      (node (ref "U2") (pin "31") (pinfunction "~{DTR}_31") (pintype "output"))
    )
    (net (code "120") (name "unconnected-(U2-~{RI}-Pad3)") (class "Default")
      (node (ref "U2") (pin "3") (pinfunction "~{RI}_3") (pintype "input"))
    )
    (net (code "121") (name "unconnected-(U2-~{RTS}-Pad32)") (class "Default")
      (node (ref "U2") (pin "32") (pinfunction "~{RTS}_32") (pintype "output"))
    )
    (net (code "122") (name "unconnected-(U6-NC-Pad7)") (class "Default")
      (node (ref "U6") (pin "7") (pinfunction "NC_7") (pintype "no_connect"))
    )
    (net (code "123") (name "unconnected-(U7-D+-PadAD6)") (class "Default")
      (node (ref "U7") (pin "AD6") (pinfunction "D+_AD6") (pintype "bidirectional"))
    )
    (net (code "124") (name "unconnected-(U7-D--PadAD4)") (class "Default")
      (node (ref "U7") (pin "AD4") (pinfunction "D-_AD4") (pintype "bidirectional"))
    )
    (net (code "125") (name "unconnected-(U7-DCCH-PadAB2)") (class "Default")
      (node (ref "U7") (pin "AB2") (pinfunction "DCCH_AB2") (pintype "bidirectional"))
    )
    (net (code "126") (name "unconnected-(U7-DEC2-PadA18)") (class "Default")
      (node (ref "U7") (pin "A18") (pinfunction "DEC2_A18") (pintype "bidirectional"))
    )
    (net (code "127") (name "unconnected-(U7-DECUSB-PadAC5)") (class "Default")
      (node (ref "U7") (pin "AC5") (pinfunction "DECUSB_AC5") (pintype "bidirectional"))
    )
    (net (code "128") (name "unconnected-(U7-P0.02{slash}AIN0-PadA12)") (class "Default")
      (node (ref "U7") (pin "A12") (pinfunction "P0.02/AIN0_A12") (pintype "bidirectional"))
    )
    (net (code "129") (name "unconnected-(U7-P0.03{slash}AIN1-PadB13)") (class "Default")
      (node (ref "U7") (pin "B13") (pinfunction "P0.03/AIN1_B13") (pintype "bidirectional"))
    )
    (net (code "130") (name "unconnected-(U7-P0.09{slash}NFC1-PadL24)") (class "Default")
      (node (ref "U7") (pin "L24") (pinfunction "P0.09/NFC1_L24") (pintype "bidirectional"))
    )
    (net (code "131") (name "unconnected-(U7-P0.10{slash}NFC2-PadJ24)") (class "Default")
      (node (ref "U7") (pin "J24") (pinfunction "P0.10/NFC2_J24") (pintype "bidirectional"))
    )
    (net (code "132") (name "unconnected-(U7-P0.19-PadAC15)") (class "Default")
      (node (ref "U7") (pin "AC15") (pinfunction "P0.19_AC15") (pintype "bidirectional"))
    )
    (net (code "133") (name "unconnected-(U7-P0.21-PadAC17)") (class "Default")
      (node (ref "U7") (pin "AC17") (pinfunction "P0.21_AC17") (pintype "bidirectional"))
    )
    (net (code "134") (name "unconnected-(U7-P0.23-PadAC19)") (class "Default")
      (node (ref "U7") (pin "AC19") (pinfunction "P0.23_AC19") (pintype "bidirectional"))
    )
    (net (code "135") (name "unconnected-(U7-P0.25-PadAC21)") (class "Default")
      (node (ref "U7") (pin "AC21") (pinfunction "P0.25_AC21") (pintype "bidirectional"))
    )
    (net (code "136") (name "unconnected-(U7-P0.28{slash}AIN4-PadB11)") (class "Default")
      (node (ref "U7") (pin "B11") (pinfunction "P0.28/AIN4_B11") (pintype "bidirectional"))
    )
    (net (code "137") (name "unconnected-(U7-P0.29{slash}AIN5-PadA10)") (class "Default")
      (node (ref "U7") (pin "A10") (pinfunction "P0.29/AIN5_A10") (pintype "bidirectional"))
    )
    (net (code "138") (name "unconnected-(U7-P0.31{slash}AIN7-PadA8)") (class "Default")
      (node (ref "U7") (pin "A8") (pinfunction "P0.31/AIN7_A8") (pintype "bidirectional"))
    )
    (net (code "139") (name "unconnected-(U7-P1.01-PadY23)") (class "Default")
      (node (ref "U7") (pin "Y23") (pinfunction "P1.01_Y23") (pintype "bidirectional"))
    )
    (net (code "140") (name "unconnected-(U7-P1.02-PadW24)") (class "Default")
      (node (ref "U7") (pin "W24") (pinfunction "P1.02_W24") (pintype "bidirectional"))
    )
    (net (code "141") (name "unconnected-(U7-P1.03-PadV23)") (class "Default")
      (node (ref "U7") (pin "V23") (pinfunction "P1.03_V23") (pintype "bidirectional"))
    )
    (net (code "142") (name "unconnected-(U7-P1.04-PadU24)") (class "Default")
      (node (ref "U7") (pin "U24") (pinfunction "P1.04_U24") (pintype "bidirectional"))
    )
    (net (code "143") (name "unconnected-(U7-P1.05-PadT23)") (class "Default")
      (node (ref "U7") (pin "T23") (pinfunction "P1.05_T23") (pintype "bidirectional"))
    )
    (net (code "144") (name "unconnected-(U7-P1.06-PadR24)") (class "Default")
      (node (ref "U7") (pin "R24") (pinfunction "P1.06_R24") (pintype "bidirectional"))
    )
    (net (code "145") (name "unconnected-(U7-P1.07-PadP23)") (class "Default")
      (node (ref "U7") (pin "P23") (pinfunction "P1.07_P23") (pintype "bidirectional"))
    )
    (net (code "146") (name "unconnected-(U7-P1.10-PadA20)") (class "Default")
      (node (ref "U7") (pin "A20") (pinfunction "P1.10_A20") (pintype "bidirectional"))
    )
    (net (code "147") (name "unconnected-(U7-P1.11-PadB19)") (class "Default")
      (node (ref "U7") (pin "B19") (pinfunction "P1.11_B19") (pintype "bidirectional"))
    )
    (net (code "148") (name "unconnected-(U7-P1.12-PadB17)") (class "Default")
      (node (ref "U7") (pin "B17") (pinfunction "P1.12_B17") (pintype "bidirectional"))
    )
    (net (code "149") (name "unconnected-(U7-P1.13-PadA16)") (class "Default")
      (node (ref "U7") (pin "A16") (pinfunction "P1.13_A16") (pintype "bidirectional"))
    )
    (net (code "150") (name "unconnected-(U7-P1.14-PadB15)") (class "Default")
      (node (ref "U7") (pin "B15") (pinfunction "P1.14_B15") (pintype "bidirectional"))
    )
    (net (code "151") (name "unconnected-(U7-P1.15-PadA14)") (class "Default")
      (node (ref "U7") (pin "A14") (pinfunction "P1.15_A14") (pintype "bidirectional"))
    )
    (net (code "152") (name "unconnected-(U10-PA0-Pad10)") (class "Default")
      (node (ref "U10") (pin "10") (pinfunction "PA0_10") (pintype "bidirectional"))
    )
    (net (code "153") (name "unconnected-(U10-PA1-Pad11)") (class "Default")
      (node (ref "U10") (pin "11") (pinfunction "PA1_11") (pintype "bidirectional"))
    )
    (net (code "154") (name "unconnected-(U10-PA3-Pad13)") (class "Default")
      (node (ref "U10") (pin "13") (pinfunction "PA3_13") (pintype "bidirectional"))
    )
    (net (code "155") (name "unconnected-(U10-PA11-Pad32)") (class "Default")
      (node (ref "U10") (pin "32") (pinfunction "PA11_32") (pintype "bidirectional"))
    )
    (net (code "156") (name "unconnected-(U10-PA12-Pad33)") (class "Default")
      (node (ref "U10") (pin "33") (pinfunction "PA12_33") (pintype "bidirectional"))
    )
    (net (code "157") (name "unconnected-(U10-PA15-Pad38)") (class "Default")
      (node (ref "U10") (pin "38") (pinfunction "PA15_38") (pintype "bidirectional"))
    )
    (net (code "158") (name "unconnected-(U10-PB8-Pad45)") (class "Default")
      (node (ref "U10") (pin "45") (pinfunction "PB8_45") (pintype "bidirectional"))
    )
    (net (code "159") (name "unconnected-(U10-PB9-Pad46)") (class "Default")
      (node (ref "U10") (pin "46") (pinfunction "PB9_46") (pintype "bidirectional"))
    )
    (net (code "160") (name "unconnected-(U10-PB10-Pad21)") (class "Default")
      (node (ref "U10") (pin "21") (pinfunction "PB10_21") (pintype "bidirectional"))
    )
    (net (code "161") (name "unconnected-(U10-PB11-Pad22)") (class "Default")
      (node (ref "U10") (pin "22") (pinfunction "PB11_22") (pintype "bidirectional"))
    )
    (net (code "162") (name "unconnected-(U10-PC13-Pad2)") (class "Default")
      (node (ref "U10") (pin "2") (pinfunction "PC13_2") (pintype "bidirectional"))
    )
    (net (code "163") (name "unconnected-(U10-PC14-OSC32_IN-Pad3)") (class "Default")
      (node (ref "U10") (pin "3") (pinfunction "PC14-OSC32_IN_3") (pintype "bidirectional"))
    )
    (net (code "164") (name "unconnected-(U10-PC15-OSC32_OUT-Pad4)") (class "Default")
      (node (ref "U10") (pin "4") (pinfunction "PC15-OSC32_OUT_4") (pintype "bidirectional"))
    )
    (net (code "165") (name "~{DW_RST}") (class "Default")
      (node (ref "U1") (pin "27") (pinfunction "~{RST}_27") (pintype "bidirectional"))
      (node (ref "U10") (pin "18") (pinfunction "PB0_18") (pintype "bidirectional"))
    )
    (net (code "166") (name "~{DW_SPI_CS}") (class "Default")
      (node (ref "U1") (pin "24") (pinfunction "~{SPICS}_24") (pintype "input"))
      (node (ref "U10") (pin "14") (pinfunction "PA4_14") (pintype "bidirectional"))
    )
    (net (code "167") (name "~{FT_RST}") (class "Default")
      (node (ref "U2") (pin "18") (pinfunction "~{RESET}_18") (pintype "input"))
      (node (ref "U7") (pin "P2") (pinfunction "P1.08_P2") (pintype "bidirectional"))
    )
    (net (code "168") (name "~{NRF_CS_IMU}") (class "Default")
      (node (ref "U3") (pin "2") (pinfunction "CS_2") (pintype "bidirectional"))
      (node (ref "U7") (pin "AC11") (pinfunction "P0.16_AC11") (pintype "bidirectional"))
    )
    (net (code "169") (name "~{NRF_CS_SD}") (class "Default")
      (node (ref "J2") (pin "2") (pinfunction "DATA3-CD/CS_N_2") (pintype "bidirectional"))
      (node (ref "R13") (pin "1") (pinfunction "1_1") (pintype "passive"))
      (node (ref "U7") (pin "AD16") (pinfunction "P0.20_AD16") (pintype "bidirectional"))
    )
    (net (code "170") (name "~{NRF_RST}") (class "Default")
      (node (ref "J4") (pin "3") (pinfunction "~{RESET}_3") (pintype "bidirectional"))
      (node (ref "U7") (pin "AC13") (pinfunction "P0.18_AC13") (pintype "bidirectional"))
    )
    (net (code "171") (name "~{SD_DETECT}") (class "Default")
      (node (ref "J2") (pin "A") (pinfunction "A_A") (pintype "bidirectional"))
      (node (ref "R19") (pin "1") (pinfunction "1_1") (pintype "passive"))
      (node (ref "U7") (pin "AD22") (pinfunction "P1.00_AD22") (pintype "bidirectional"))
    )
    (net (code "172") (name "~{STM_RST}") (class "Default")
      (node (ref "J5") (pin "3") (pinfunction "~{RESET}_3") (pintype "bidirectional"))
      (node (ref "U10") (pin "7") (pinfunction "~{RST}_7") (pintype "bidirectional"))
    )
  )
)
